# module.net
KiCad netlist of a schematic drawn in EAGLE
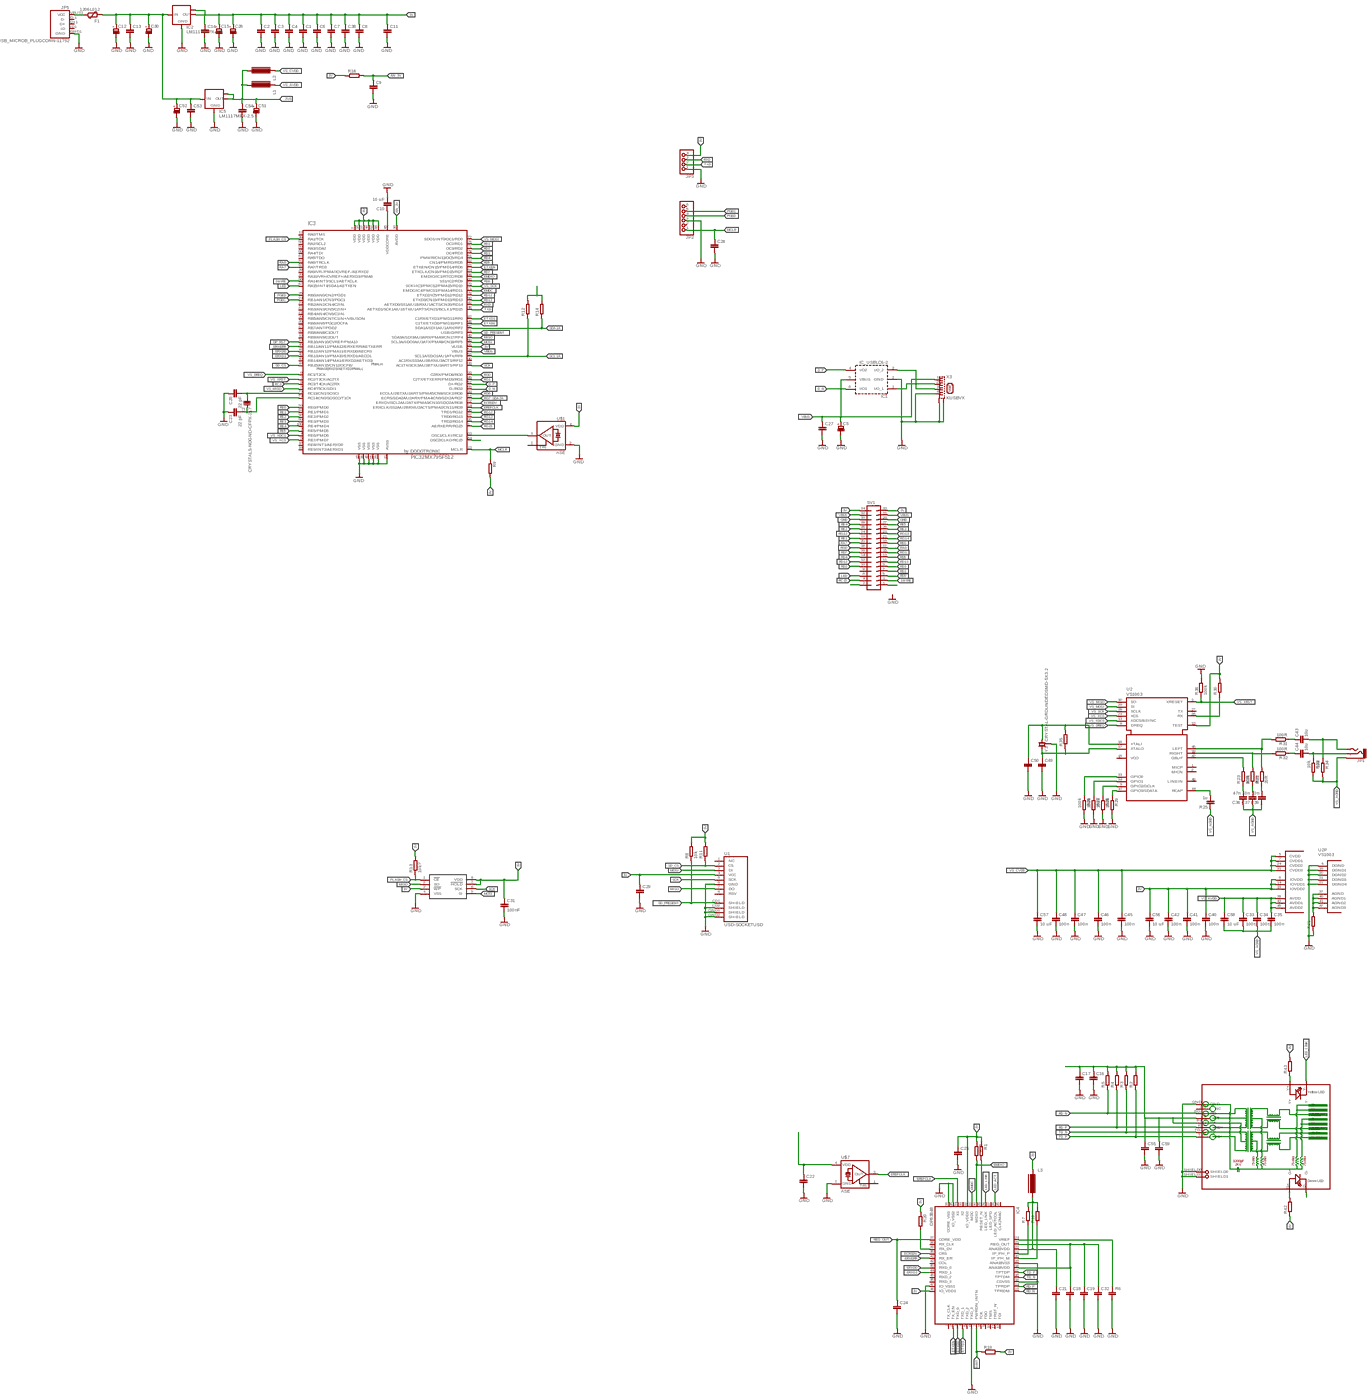
[diagram p0: schematic, sheet 1, overview]
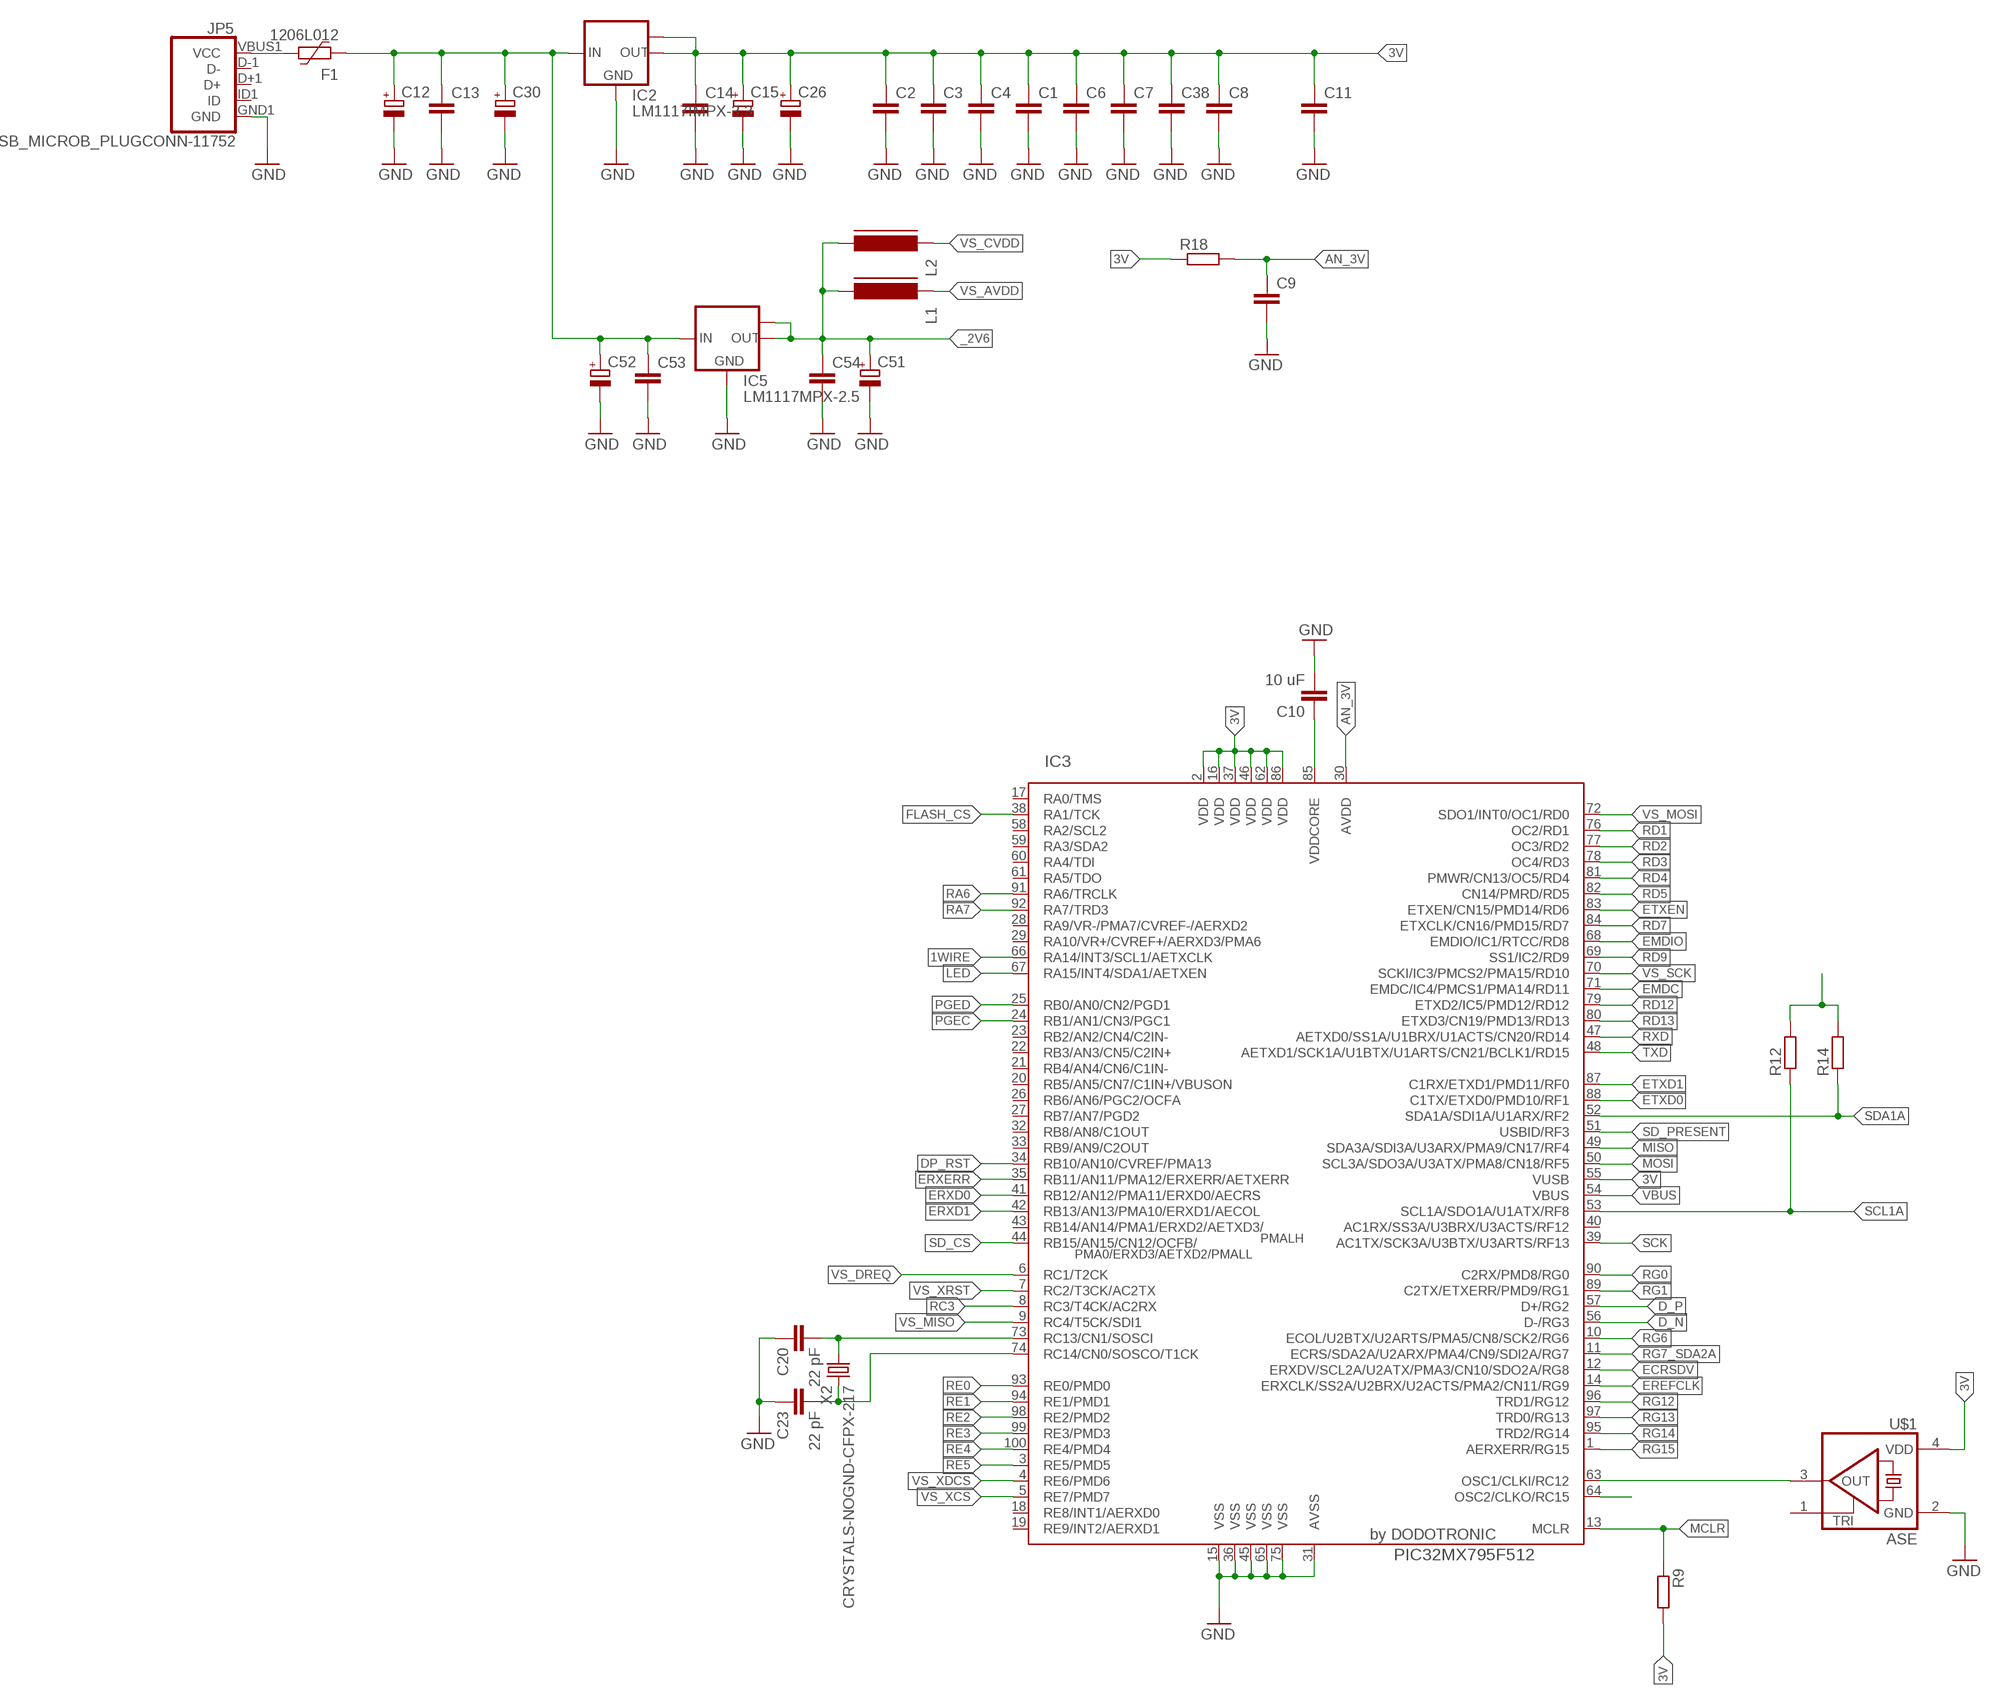
[diagram p1: schematic, sheet 1, part 1 of 4]
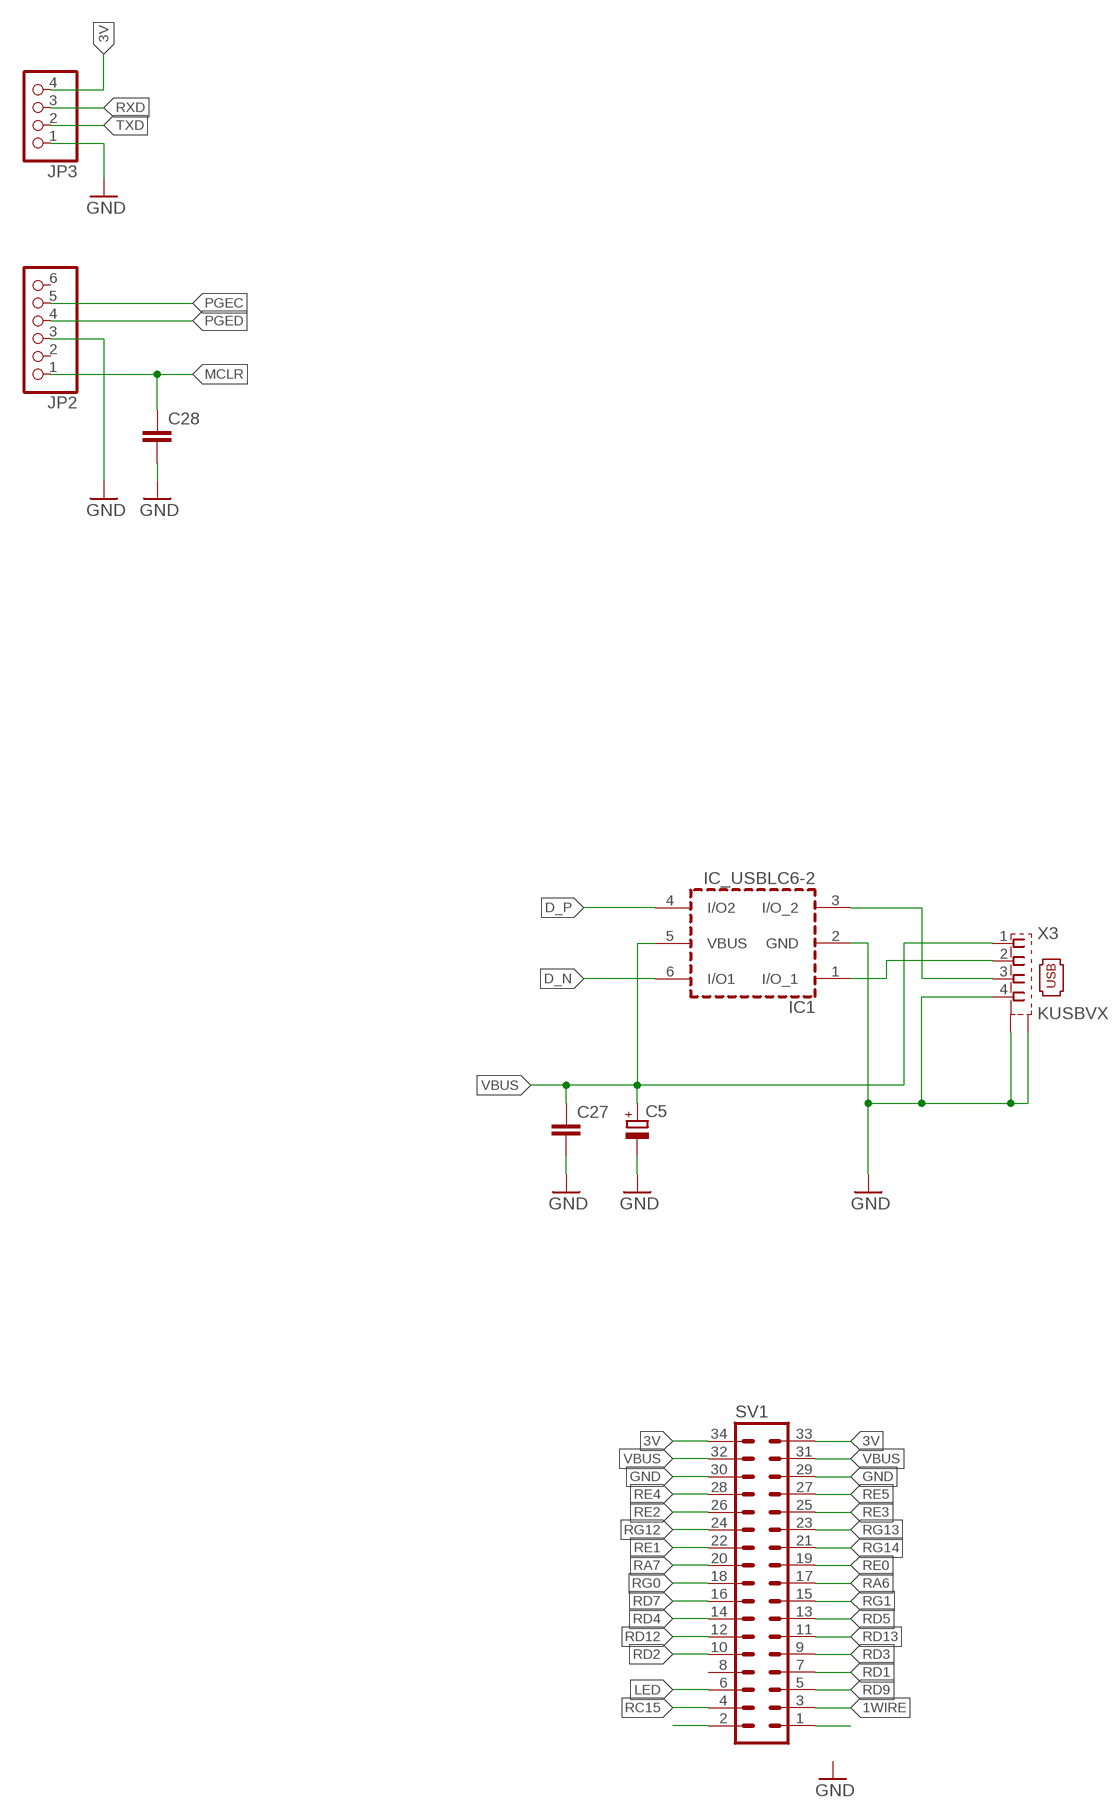
[diagram p2: schematic, sheet 1, part 2 of 4]
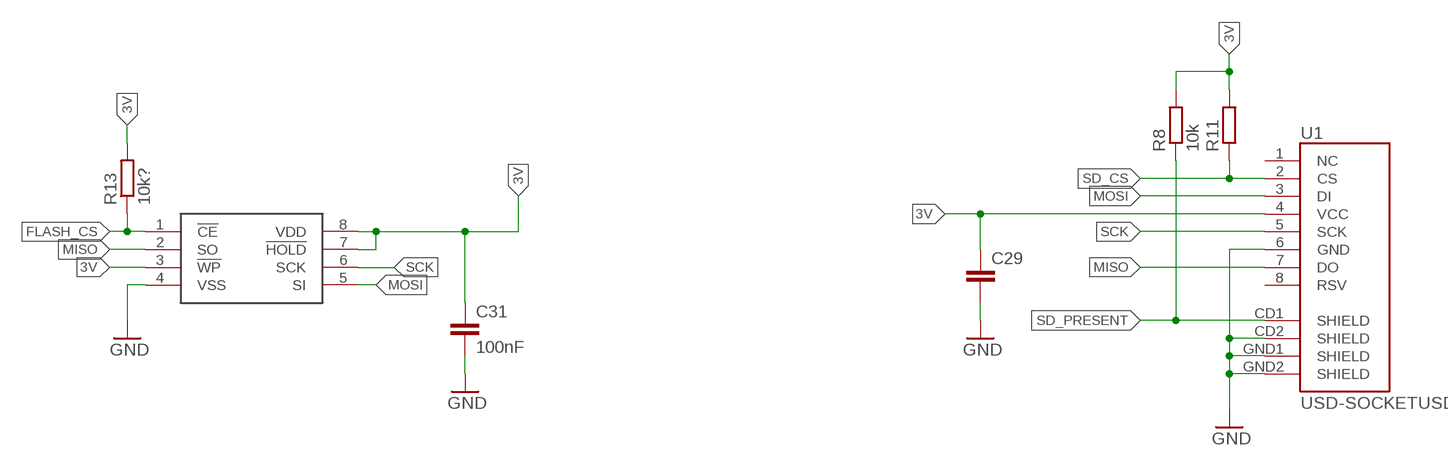
[diagram p3: schematic, sheet 1, part 3 of 4]
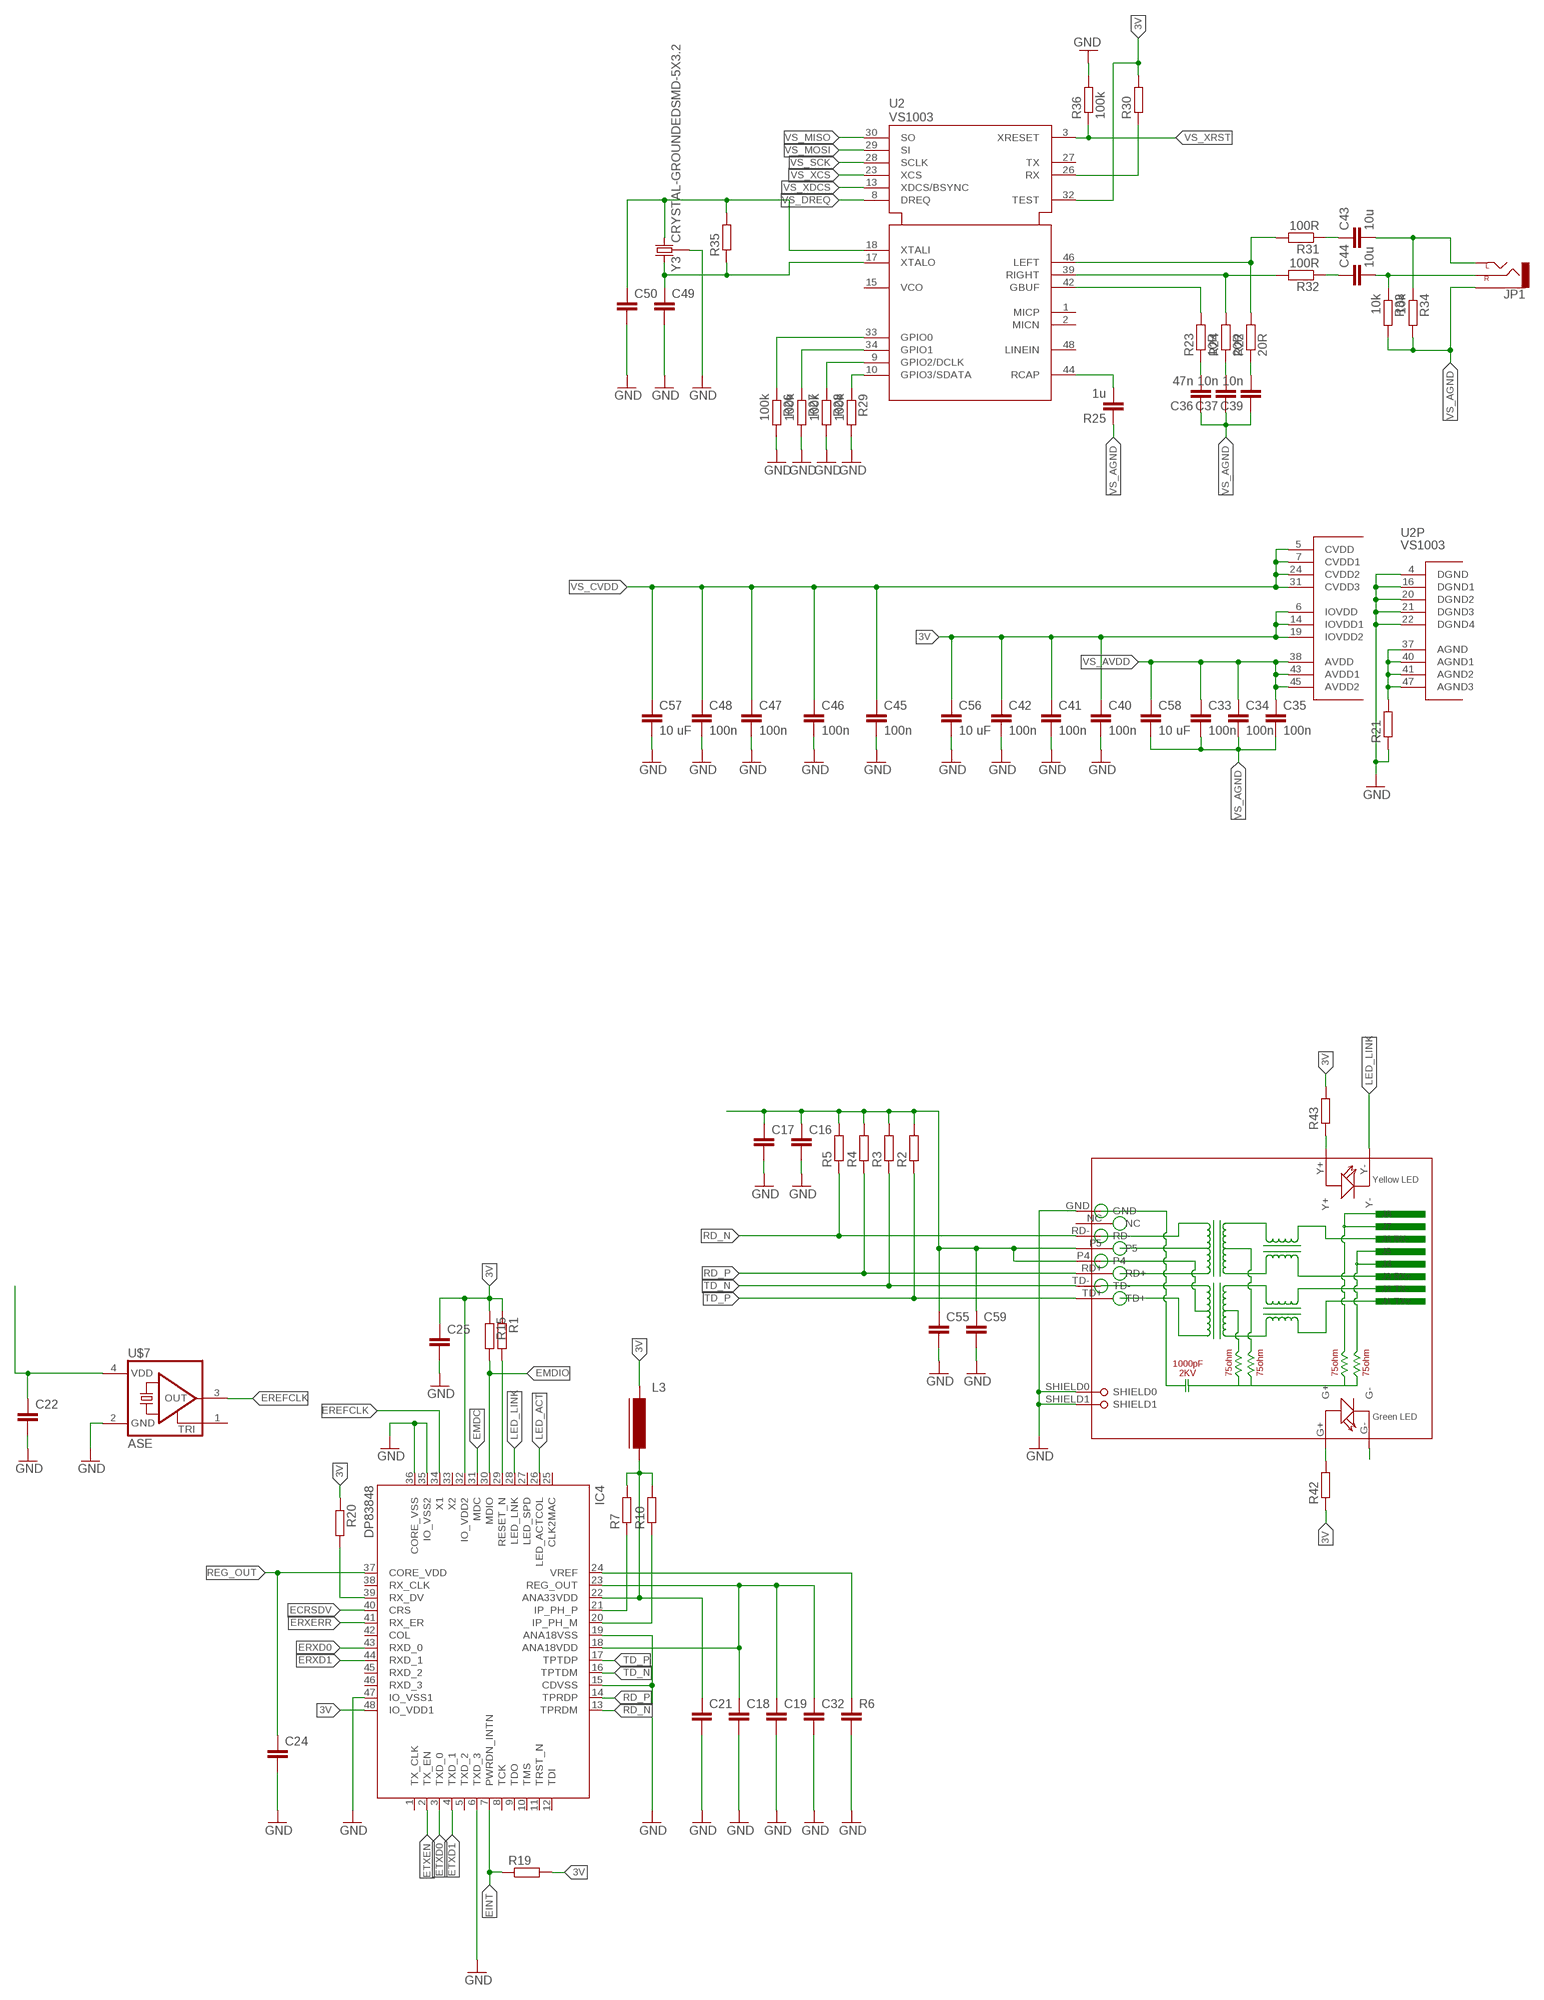
[diagram p4: schematic, sheet 1, part 4 of 4]

(export (version "E")
  (design (tool "Eeschema 10.0.6"))
  (components
    (comp (ref "C1")
      (value "C-EUC0402")
      (footprint "eagle-import:C0402")
      (libsource (lib "eagle-import") (part "C-EUC0402"))
    )
    (comp (ref "C2")
      (value "C-EUC0402")
      (footprint "eagle-import:C0402")
      (libsource (lib "eagle-import") (part "C-EUC0402"))
    )
    (comp (ref "C3")
      (value "C-EUC0402")
      (footprint "eagle-import:C0402")
      (libsource (lib "eagle-import") (part "C-EUC0402"))
    )
    (comp (ref "C4")
      (value "C-EUC0402")
      (footprint "eagle-import:C0402")
      (libsource (lib "eagle-import") (part "C-EUC0402"))
    )
    (comp (ref "C5")
      (value "CPOL-EUSMCA")
      (footprint "eagle-import:SMC_A")
      (libsource (lib "eagle-import") (part "CPOL-EUSMCA"))
    )
    (comp (ref "C6")
      (value "C-EUC0402")
      (footprint "eagle-import:C0402")
      (libsource (lib "eagle-import") (part "C-EUC0402"))
    )
    (comp (ref "C7")
      (value "C-EUC0402")
      (footprint "eagle-import:C0402")
      (libsource (lib "eagle-import") (part "C-EUC0402"))
    )
    (comp (ref "C8")
      (value "C-EUC0402")
      (footprint "eagle-import:C0402")
      (libsource (lib "eagle-import") (part "C-EUC0402"))
    )
    (comp (ref "C9")
      (value "C-EUC0402")
      (footprint "eagle-import:C0402")
      (libsource (lib "eagle-import") (part "C-EUC0402"))
    )
    (comp (ref "C10")
      (value "10 uF")
      (footprint "eagle-import:C0603")
      (libsource (lib "eagle-import") (part "C-EUC0603"))
    )
    (comp (ref "C11")
      (value "C-EUC0402")
      (footprint "eagle-import:C0402")
      (libsource (lib "eagle-import") (part "C-EUC0402"))
    )
    (comp (ref "C12")
      (value "CPOL-EUSMCB")
      (footprint "eagle-import:SMC_B")
      (libsource (lib "eagle-import") (part "CPOL-EUSMCB"))
    )
    (comp (ref "C13")
      (value "C-EUC0603")
      (footprint "eagle-import:C0603")
      (libsource (lib "eagle-import") (part "C-EUC0603"))
    )
    (comp (ref "C14")
      (value "C-EUC0603")
      (footprint "eagle-import:C0603")
      (libsource (lib "eagle-import") (part "C-EUC0603"))
    )
    (comp (ref "C15")
      (value "CPOL-EUSMCB")
      (footprint "eagle-import:SMC_B")
      (libsource (lib "eagle-import") (part "CPOL-EUSMCB"))
    )
    (comp (ref "C16")
      (value "C-EUC0603")
      (footprint "eagle-import:C0603")
      (libsource (lib "eagle-import") (part "C-EUC0603"))
    )
    (comp (ref "C17")
      (value "C-EUC0603")
      (footprint "eagle-import:C0603")
      (libsource (lib "eagle-import") (part "C-EUC0603"))
    )
    (comp (ref "C18")
      (value "C-EUC0402")
      (footprint "eagle-import:C0402")
      (libsource (lib "eagle-import") (part "C-EUC0402"))
    )
    (comp (ref "C19")
      (value "C-EUC0402")
      (footprint "eagle-import:C0402")
      (libsource (lib "eagle-import") (part "C-EUC0402"))
    )
    (comp (ref "C20")
      (value "22 pF")
      (footprint "eagle-import:C0603")
      (libsource (lib "eagle-import") (part "C-EUC0603"))
    )
    (comp (ref "C21")
      (value "C-EUC0402")
      (footprint "eagle-import:C0402")
      (libsource (lib "eagle-import") (part "C-EUC0402"))
    )
    (comp (ref "C22")
      (value "C-EUC0402")
      (footprint "eagle-import:C0402")
      (libsource (lib "eagle-import") (part "C-EUC0402"))
    )
    (comp (ref "C23")
      (value "22 pF")
      (footprint "eagle-import:C0603")
      (libsource (lib "eagle-import") (part "C-EUC0603"))
    )
    (comp (ref "C24")
      (value "C-EUC0603")
      (footprint "eagle-import:C0603")
      (libsource (lib "eagle-import") (part "C-EUC0603"))
    )
    (comp (ref "C25")
      (value "C-EUC0603")
      (footprint "eagle-import:C0603")
      (libsource (lib "eagle-import") (part "C-EUC0603"))
    )
    (comp (ref "C26")
      (value "CPOL-EUSMCA")
      (footprint "eagle-import:SMC_A")
      (libsource (lib "eagle-import") (part "CPOL-EUSMCA"))
    )
    (comp (ref "C27")
      (value "C-EUC0603")
      (footprint "eagle-import:C0603")
      (libsource (lib "eagle-import") (part "C-EUC0603"))
    )
    (comp (ref "C28")
      (value "C-EUC0603")
      (footprint "eagle-import:C0603")
      (libsource (lib "eagle-import") (part "C-EUC0603"))
    )
    (comp (ref "C29")
      (value "C-EUC0603")
      (footprint "eagle-import:C0603")
      (libsource (lib "eagle-import") (part "C-EUC0603"))
    )
    (comp (ref "C30")
      (value "CPOL-EUSMCA")
      (footprint "eagle-import:SMC_A")
      (libsource (lib "eagle-import") (part "CPOL-EUSMCA"))
    )
    (comp (ref "C31")
      (value "100nF")
      (footprint "eagle-import:C0603")
      (libsource (lib "eagle-import") (part "C-EUC0603"))
    )
    (comp (ref "C32")
      (value "C-EUC0603")
      (footprint "eagle-import:C0603")
      (libsource (lib "eagle-import") (part "C-EUC0603"))
    )
    (comp (ref "C33")
      (value "100n")
      (footprint "eagle-import:C0603")
      (libsource (lib "eagle-import") (part "C-EUC0603"))
    )
    (comp (ref "C34")
      (value "100n")
      (footprint "eagle-import:C0603")
      (libsource (lib "eagle-import") (part "C-EUC0603"))
    )
    (comp (ref "C35")
      (value "100n")
      (footprint "eagle-import:C0603")
      (libsource (lib "eagle-import") (part "C-EUC0603"))
    )
    (comp (ref "C36")
      (value "47n")
      (footprint "eagle-import:C0603")
      (libsource (lib "eagle-import") (part "C-EUC0603"))
    )
    (comp (ref "C37")
      (value "10n")
      (footprint "eagle-import:C0603")
      (libsource (lib "eagle-import") (part "C-EUC0603"))
    )
    (comp (ref "C38")
      (value "C-EUC0402")
      (footprint "eagle-import:C0402")
      (libsource (lib "eagle-import") (part "C-EUC0402"))
    )
    (comp (ref "C39")
      (value "10n")
      (footprint "eagle-import:C0603")
      (libsource (lib "eagle-import") (part "C-EUC0603"))
    )
    (comp (ref "C40")
      (value "100n")
      (footprint "eagle-import:C0402")
      (libsource (lib "eagle-import") (part "C-EUC0402"))
    )
    (comp (ref "C41")
      (value "100n")
      (footprint "eagle-import:C0402")
      (libsource (lib "eagle-import") (part "C-EUC0402"))
    )
    (comp (ref "C42")
      (value "100n")
      (footprint "eagle-import:C0402")
      (libsource (lib "eagle-import") (part "C-EUC0402"))
    )
    (comp (ref "C43")
      (value "10u")
      (footprint "eagle-import:C0603")
      (libsource (lib "eagle-import") (part "C-EUC0603"))
    )
    (comp (ref "C44")
      (value "10u")
      (footprint "eagle-import:C0603")
      (libsource (lib "eagle-import") (part "C-EUC0603"))
    )
    (comp (ref "C45")
      (value "100n")
      (footprint "eagle-import:C0402")
      (libsource (lib "eagle-import") (part "C-EUC0402"))
    )
    (comp (ref "C46")
      (value "100n")
      (footprint "eagle-import:C0603")
      (libsource (lib "eagle-import") (part "C-EUC0603"))
    )
    (comp (ref "C47")
      (value "100n")
      (footprint "eagle-import:C0603")
      (libsource (lib "eagle-import") (part "C-EUC0603"))
    )
    (comp (ref "C48")
      (value "100n")
      (footprint "eagle-import:C0603")
      (libsource (lib "eagle-import") (part "C-EUC0603"))
    )
    (comp (ref "C49")
      (value "C-EUC0603")
      (footprint "eagle-import:C0603")
      (libsource (lib "eagle-import") (part "C-EUC0603"))
    )
    (comp (ref "C50")
      (value "C-EUC0603")
      (footprint "eagle-import:C0603")
      (libsource (lib "eagle-import") (part "C-EUC0603"))
    )
    (comp (ref "C51")
      (value "CPOL-EUSMCB")
      (footprint "eagle-import:SMC_B")
      (libsource (lib "eagle-import") (part "CPOL-EUSMCB"))
    )
    (comp (ref "C52")
      (value "CPOL-EUSMCB")
      (footprint "eagle-import:SMC_B")
      (libsource (lib "eagle-import") (part "CPOL-EUSMCB"))
    )
    (comp (ref "C53")
      (value "C-EUC1206")
      (footprint "eagle-import:C1206")
      (libsource (lib "eagle-import") (part "C-EUC1206"))
    )
    (comp (ref "C54")
      (value "C-EUC1206")
      (footprint "eagle-import:C1206")
      (libsource (lib "eagle-import") (part "C-EUC1206"))
    )
    (comp (ref "C55")
      (value "C-EUC0603")
      (footprint "eagle-import:C0603")
      (libsource (lib "eagle-import") (part "C-EUC0603"))
    )
    (comp (ref "C56")
      (value "10 uF")
      (footprint "eagle-import:C0603")
      (libsource (lib "eagle-import") (part "C-EUC0603"))
    )
    (comp (ref "C57")
      (value "10 uF")
      (footprint "eagle-import:C0603")
      (libsource (lib "eagle-import") (part "C-EUC0603"))
    )
    (comp (ref "C58")
      (value "10 uF")
      (footprint "eagle-import:C0603")
      (libsource (lib "eagle-import") (part "C-EUC0603"))
    )
    (comp (ref "C59")
      (value "C-EUC0603")
      (footprint "eagle-import:C0603")
      (libsource (lib "eagle-import") (part "C-EUC0603"))
    )
    (comp (ref "F1")
      (value "1206L012")
      (footprint "eagle-import:1206L")
      (fields (field (name "MF") "Littelfuse"))
      (libsource (lib "eagle-import") (part "?1206L012"))
    )
    (comp (ref "IC1")
      (value "IC_USBLC6-2")
      (footprint "eagle-import:SOT-23-6L")
      (libsource (lib "eagle-import") (part "IC_USBLC6-2"))
    )
    (comp (ref "IC2")
      (value "LM1117IMPX-3.3")
      (footprint "eagle-import:SOT223")
      (libsource (lib "eagle-import") (part "LM1117IMPX-3.3"))
    )
    (comp (ref "IC3")
      (value "PIC32MX795F512")
      (footprint "eagle-import:TQFP100_12X12")
      (libsource (lib "eagle-import") (part "PIC32MX795F512"))
    )
    (comp (ref "IC4")
      (value "DP83848")
      (footprint "eagle-import:LQFP48")
      (fields (field (name "MPN") "DP83848VYB"))
      (libsource (lib "eagle-import") (part "DP83848"))
    )
    (comp (ref "IC5")
      (value "LM1117MPX-2.5")
      (footprint "eagle-import:SOT223")
      (libsource (lib "eagle-import") (part "LM1117MPX-2.5"))
    )
    (comp (ref "JP1")
      (value "AUDIO-JACKAUDIO_JACK2")
      (footprint "eagle-import:AUDIO-JACK2")
      (libsource (lib "eagle-import") (part "AUDIO-JACKAUDIO_JACK2"))
    )
    (comp (ref "JP2")
      (value "PINHD-1X6")
      (footprint "eagle-import:1X06")
      (libsource (lib "eagle-import") (part "PINHD-1X6"))
    )
    (comp (ref "JP3")
      (value "PINHD-1X4")
      (footprint "eagle-import:1X04")
      (libsource (lib "eagle-import") (part "PINHD-1X4"))
    )
    (comp (ref "JP5")
      (value "USB_MICROB_PLUGCONN-11752")
      (footprint "eagle-import:USB-B-MICRO-SMD_V03")
      (libsource (lib "eagle-import") (part "USB_MICROB_PLUGCONN-11752"))
    )
    (comp (ref "L1")
      (value "FERRITE-0805")
      (footprint "eagle-import:FB805")
      (libsource (lib "eagle-import") (part "FERRITE-0805"))
    )
    (comp (ref "L2")
      (value "FERRITE-0805")
      (footprint "eagle-import:FB805")
      (libsource (lib "eagle-import") (part "FERRITE-0805"))
    )
    (comp (ref "L3")
      (value "FERRITE-0805")
      (footprint "eagle-import:FB805")
      (libsource (lib "eagle-import") (part "FERRITE-0805"))
    )
    (comp (ref "R1")
      (value "R-EU_R0402")
      (footprint "eagle-import:R0402")
      (libsource (lib "eagle-import") (part "R-EU_R0402"))
    )
    (comp (ref "R2")
      (value "R-EU_R0603")
      (footprint "eagle-import:R0603")
      (libsource (lib "eagle-import") (part "R-EU_R0603"))
    )
    (comp (ref "R3")
      (value "R-EU_R0603")
      (footprint "eagle-import:R0603")
      (libsource (lib "eagle-import") (part "R-EU_R0603"))
    )
    (comp (ref "R4")
      (value "R-EU_R0603")
      (footprint "eagle-import:R0603")
      (libsource (lib "eagle-import") (part "R-EU_R0603"))
    )
    (comp (ref "R5")
      (value "R-EU_R0603")
      (footprint "eagle-import:R0603")
      (libsource (lib "eagle-import") (part "R-EU_R0603"))
    )
    (comp (ref "R6")
      (value "C-EUC0603")
      (footprint "eagle-import:C0603")
      (libsource (lib "eagle-import") (part "C-EUC0603"))
    )
    (comp (ref "R7")
      (value "R-EU_R0402")
      (footprint "eagle-import:R0402")
      (libsource (lib "eagle-import") (part "R-EU_R0402"))
    )
    (comp (ref "R8")
      (value "10k")
      (footprint "eagle-import:R0603")
      (libsource (lib "eagle-import") (part "R-EU_R0603"))
    )
    (comp (ref "R9")
      (value "R-EU_R0603")
      (footprint "eagle-import:R0603")
      (libsource (lib "eagle-import") (part "R-EU_R0603"))
    )
    (comp (ref "R10")
      (value "R-EU_R0402")
      (footprint "eagle-import:R0402")
      (libsource (lib "eagle-import") (part "R-EU_R0402"))
    )
    (comp (ref "R11")
      (value "R-EU_R0603")
      (footprint "eagle-import:R0603")
      (libsource (lib "eagle-import") (part "R-EU_R0603"))
    )
    (comp (ref "R12")
      (value "R-EU_R0603")
      (footprint "eagle-import:R0603")
      (libsource (lib "eagle-import") (part "R-EU_R0603"))
    )
    (comp (ref "R13")
      (value "10k?")
      (footprint "eagle-import:R0603")
      (libsource (lib "eagle-import") (part "R-EU_R0603"))
    )
    (comp (ref "R14")
      (value "R-EU_R0402")
      (footprint "eagle-import:R0402")
      (libsource (lib "eagle-import") (part "R-EU_R0402"))
    )
    (comp (ref "R15")
      (value "R-EU_R0603")
      (footprint "eagle-import:R0603")
      (libsource (lib "eagle-import") (part "R-EU_R0603"))
    )
    (comp (ref "R18")
      (value "R-EU_R0805")
      (footprint "eagle-import:R0805")
      (libsource (lib "eagle-import") (part "R-EU_R0805"))
    )
    (comp (ref "R19")
      (value "R-EU_R0402")
      (footprint "eagle-import:R0402")
      (libsource (lib "eagle-import") (part "R-EU_R0402"))
    )
    (comp (ref "R20")
      (value "R-EU_R0603")
      (footprint "eagle-import:R0603")
      (libsource (lib "eagle-import") (part "R-EU_R0603"))
    )
    (comp (ref "R21")
      (value "R-EU_R0603")
      (footprint "eagle-import:R0603")
      (libsource (lib "eagle-import") (part "R-EU_R0603"))
    )
    (comp (ref "R22")
      (value "20R")
      (footprint "eagle-import:R0603")
      (libsource (lib "eagle-import") (part "R-EU_R0603"))
    )
    (comp (ref "R23")
      (value "10R")
      (footprint "eagle-import:R0603")
      (libsource (lib "eagle-import") (part "R-EU_R0603"))
    )
    (comp (ref "R24")
      (value "20R")
      (footprint "eagle-import:R0603")
      (libsource (lib "eagle-import") (part "R-EU_R0603"))
    )
    (comp (ref "R25")
      (value "1u")
      (footprint "eagle-import:C0603")
      (libsource (lib "eagle-import") (part "C-EUC0603"))
    )
    (comp (ref "R26")
      (value "100k")
      (footprint "eagle-import:R0402")
      (libsource (lib "eagle-import") (part "R-EU_R0402"))
    )
    (comp (ref "R27")
      (value "100k")
      (footprint "eagle-import:R0402")
      (libsource (lib "eagle-import") (part "R-EU_R0402"))
    )
    (comp (ref "R28")
      (value "100k")
      (footprint "eagle-import:R0402")
      (libsource (lib "eagle-import") (part "R-EU_R0402"))
    )
    (comp (ref "R29")
      (value "100k")
      (footprint "eagle-import:R0402")
      (libsource (lib "eagle-import") (part "R-EU_R0402"))
    )
    (comp (ref "R30")
      (value "R-EU_0204/7")
      (footprint "eagle-import:0204_7")
      (libsource (lib "eagle-import") (part "R-EU_0204/7"))
    )
    (comp (ref "R31")
      (value "100R")
      (footprint "eagle-import:R0603")
      (libsource (lib "eagle-import") (part "R-EU_R0603"))
    )
    (comp (ref "R32")
      (value "100R")
      (footprint "eagle-import:R0603")
      (libsource (lib "eagle-import") (part "R-EU_R0603"))
    )
    (comp (ref "R33")
      (value "10k")
      (footprint "eagle-import:R0603")
      (libsource (lib "eagle-import") (part "R-EU_R0603"))
    )
    (comp (ref "R34")
      (value "10k")
      (footprint "eagle-import:R0603")
      (libsource (lib "eagle-import") (part "R-EU_R0603"))
    )
    (comp (ref "R35")
      (value "R-EU_R0603")
      (footprint "eagle-import:R0603")
      (libsource (lib "eagle-import") (part "R-EU_R0603"))
    )
    (comp (ref "R36")
      (value "100k")
      (footprint "eagle-import:R0603")
      (libsource (lib "eagle-import") (part "R-EU_R0603"))
    )
    (comp (ref "R42")
      (value "R-EU_R0603")
      (footprint "eagle-import:R0603")
      (libsource (lib "eagle-import") (part "R-EU_R0603"))
    )
    (comp (ref "R43")
      (value "R-EU_R0603")
      (footprint "eagle-import:R0603")
      (libsource (lib "eagle-import") (part "R-EU_R0603"))
    )
    (comp (ref "RJ1")
      (value "HR911105A")
      (footprint "eagle-import:HR911105A")
      (libsource (lib "eagle-import") (part "HR911105A"))
    )
    (comp (ref "SV1")
      (value "ML34L")
      (footprint "eagle-import:ML34L")
      (libsource (lib "eagle-import") (part "ML34L"))
    )
    (comp (ref "U$1")
      (value "ASE")
      (footprint "eagle-import:ASE")
      (libsource (lib "eagle-import") (part "ASE"))
    )
    (comp (ref "U$2")
      (value "SST25VF016BSO8M")
      (footprint "eagle-import:SO-08M")
      (libsource (lib "eagle-import") (part "SST25VF016BSO8M"))
    )
    (comp (ref "U$7")
      (value "ASE")
      (footprint "eagle-import:ASE")
      (libsource (lib "eagle-import") (part "ASE"))
    )
    (comp (ref "U1")
      (value "USD-SOCKETUSD")
      (footprint "eagle-import:USD-SOCKET-PP")
      (libsource (lib "eagle-import") (part "USD-SOCKETUSD"))
    )
    (comp (ref "U2")
      (value "VS1003")
      (footprint "eagle-import:LQFP48")
      (libsource (lib "eagle-import") (part "VS1003"))
    )
    (comp (ref "X2")
      (value "CRYSTALS-NOGND-CFPX-217")
      (footprint "eagle-import:3.2X1.5-2-PAD")
      (libsource (lib "eagle-import") (part "CRYSTALS-NOGND-CFPX-217"))
    )
    (comp (ref "X3")
      (value "KUSBVX")
      (footprint "eagle-import:KUSBVX")
      (libsource (lib "eagle-import") (part "KUSBVX"))
    )
    (comp (ref "Y3")
      (value "CRYSTAL-GROUNDEDSMD-5X3.2")
      (footprint "eagle-import:CRYSTAL-SMD-5X3.2-4PAD")
      (libsource (lib "eagle-import") (part "CRYSTAL-GROUNDEDSMD-5X3.2"))
    )
  )
  (nets
    (net (code "1") (name "/A3V") (class "Default")
      (node (ref "C16") (pin "1") (pinfunction "1_1") (pintype "passive"))
      (node (ref "C17") (pin "1") (pinfunction "1_1") (pintype "passive"))
      (node (ref "C21") (pin "1") (pinfunction "1_1") (pintype "passive"))
      (node (ref "C55") (pin "1") (pinfunction "1_1") (pintype "passive"))
      (node (ref "C59") (pin "1") (pinfunction "1_1") (pintype "passive"))
      (node (ref "IC4") (pin "22") (pinfunction "ANA33VDD_22") (pintype "power_in"))
      (node (ref "L3") (pin "2") (pinfunction "2_2") (pintype "passive"))
      (node (ref "R10") (pin "2") (pinfunction "2_2") (pintype "passive"))
      (node (ref "R2") (pin "2") (pinfunction "2_2") (pintype "passive"))
      (node (ref "R3") (pin "2") (pinfunction "2_2") (pintype "passive"))
      (node (ref "R4") (pin "2") (pinfunction "2_2") (pintype "passive"))
      (node (ref "R5") (pin "2") (pinfunction "2_2") (pintype "passive"))
      (node (ref "R7") (pin "2") (pinfunction "2_2") (pintype "passive"))
      (node (ref "RJ1") (pin "P4") (pinfunction "P4_P4") (pintype "bidirectional"))
      (node (ref "RJ1") (pin "P5") (pinfunction "P5_P5") (pintype "bidirectional"))
    )
    (net (code "2") (name "1WIRE") (class "Default")
      (node (ref "IC3") (pin "66") (pinfunction "RA14/INT3/SCL1/AETXCLK_66") (pintype "bidirectional"))
      (node (ref "SV1") (pin "3") (pinfunction "3_3") (pintype "passive"))
    )
    (net (code "3") (name "3V") (class "Default")
      (node (ref "C1") (pin "1") (pinfunction "1_1") (pintype "passive"))
      (node (ref "C11") (pin "1") (pinfunction "1_1") (pintype "passive"))
      (node (ref "C14") (pin "1") (pinfunction "1_1") (pintype "passive"))
      (node (ref "C15") (pin "+") (pinfunction "+_+") (pintype "passive"))
      (node (ref "C2") (pin "1") (pinfunction "1_1") (pintype "passive"))
      (node (ref "C22") (pin "1") (pinfunction "1_1") (pintype "passive"))
      (node (ref "C25") (pin "1") (pinfunction "1_1") (pintype "passive"))
      (node (ref "C26") (pin "+") (pinfunction "+_+") (pintype "passive"))
      (node (ref "C29") (pin "1") (pinfunction "1_1") (pintype "passive"))
      (node (ref "C3") (pin "1") (pinfunction "1_1") (pintype "passive"))
      (node (ref "C31") (pin "1") (pinfunction "1_1") (pintype "passive"))
      (node (ref "C38") (pin "1") (pinfunction "1_1") (pintype "passive"))
      (node (ref "C4") (pin "1") (pinfunction "1_1") (pintype "passive"))
      (node (ref "C40") (pin "1") (pinfunction "1_1") (pintype "passive"))
      (node (ref "C41") (pin "1") (pinfunction "1_1") (pintype "passive"))
      (node (ref "C42") (pin "1") (pinfunction "1_1") (pintype "passive"))
      (node (ref "C56") (pin "1") (pinfunction "1_1") (pintype "passive"))
      (node (ref "C6") (pin "1") (pinfunction "1_1") (pintype "passive"))
      (node (ref "C7") (pin "1") (pinfunction "1_1") (pintype "passive"))
      (node (ref "C8") (pin "1") (pinfunction "1_1") (pintype "passive"))
      (node (ref "IC2") (pin "2") (pinfunction "OUT_2") (pintype "passive"))
      (node (ref "IC2") (pin "TAB") (pinfunction "OUT1_TAB") (pintype "passive"))
      (node (ref "IC3") (pin "16") (pinfunction "VDD_16") (pintype "power_in"))
      (node (ref "IC3") (pin "2") (pinfunction "VDD_2") (pintype "power_in"))
      (node (ref "IC3") (pin "37") (pinfunction "VDD_37") (pintype "power_in"))
      (node (ref "IC3") (pin "46") (pinfunction "VDD_46") (pintype "power_in"))
      (node (ref "IC3") (pin "55") (pinfunction "VUSB_55") (pintype "bidirectional"))
      (node (ref "IC3") (pin "62") (pinfunction "VDD_62") (pintype "power_in"))
      (node (ref "IC3") (pin "86") (pinfunction "VDD_86") (pintype "power_in"))
      (node (ref "IC4") (pin "32") (pinfunction "IO_VDD2_32") (pintype "power_in"))
      (node (ref "IC4") (pin "48") (pinfunction "IO_VDD1_48") (pintype "power_in"))
      (node (ref "JP3") (pin "4") (pinfunction "4_4") (pintype "passive"))
      (node (ref "L3") (pin "1") (pinfunction "1_1") (pintype "passive"))
      (node (ref "R1") (pin "1") (pinfunction "1_1") (pintype "passive"))
      (node (ref "R11") (pin "2") (pinfunction "2_2") (pintype "passive"))
      (node (ref "R12") (pin "2") (pinfunction "2_2") (pintype "passive"))
      (node (ref "R13") (pin "2") (pinfunction "2_2") (pintype "passive"))
      (node (ref "R14") (pin "2") (pinfunction "2_2") (pintype "passive"))
      (node (ref "R15") (pin "1") (pinfunction "1_1") (pintype "passive"))
      (node (ref "R18") (pin "1") (pinfunction "1_1") (pintype "passive"))
      (node (ref "R19") (pin "2") (pinfunction "2_2") (pintype "passive"))
      (node (ref "R20") (pin "1") (pinfunction "1_1") (pintype "passive"))
      (node (ref "R30") (pin "2") (pinfunction "2_2") (pintype "passive"))
      (node (ref "R42") (pin "1") (pinfunction "1_1") (pintype "passive"))
      (node (ref "R43") (pin "2") (pinfunction "2_2") (pintype "passive"))
      (node (ref "R8") (pin "2") (pinfunction "2_2") (pintype "passive"))
      (node (ref "R9") (pin "2") (pinfunction "2_2") (pintype "passive"))
      (node (ref "SV1") (pin "33") (pinfunction "33_33") (pintype "passive"))
      (node (ref "SV1") (pin "34") (pinfunction "34_34") (pintype "passive"))
      (node (ref "U$1") (pin "4") (pinfunction "VDD_4") (pintype "power_in"))
      (node (ref "U$2") (pin "3") (pinfunction "~{WP}_3") (pintype "bidirectional"))
      (node (ref "U$2") (pin "7") (pinfunction "~{HOLD}_7") (pintype "bidirectional"))
      (node (ref "U$2") (pin "8") (pinfunction "VDD_8") (pintype "bidirectional"))
      (node (ref "U$7") (pin "4") (pinfunction "VDD_4") (pintype "power_in"))
      (node (ref "U1") (pin "4") (pinfunction "VCC_4") (pintype "bidirectional"))
      (node (ref "U2") (pin "14") (pinfunction "IOVDD1_14") (pintype "power_in"))
      (node (ref "U2") (pin "19") (pinfunction "IOVDD2_19") (pintype "power_in"))
      (node (ref "U2") (pin "32") (pinfunction "TEST_32") (pintype "bidirectional"))
      (node (ref "U2") (pin "6") (pinfunction "IOVDD_6") (pintype "power_in"))
    )
    (net (code "4") (name "AN_3V") (class "Default")
      (node (ref "C9") (pin "1") (pinfunction "1_1") (pintype "passive"))
      (node (ref "IC3") (pin "30") (pinfunction "AVDD_30") (pintype "bidirectional"))
      (node (ref "R18") (pin "2") (pinfunction "2_2") (pintype "passive"))
    )
    (net (code "5") (name "DP_RST") (class "Default")
      (node (ref "IC3") (pin "34") (pinfunction "RB10/AN10/CVREF/PMA13_34") (pintype "bidirectional"))
      (node (ref "IC4") (pin "29") (pinfunction "RESET_N_29") (pintype "input"))
      (node (ref "R1") (pin "2") (pinfunction "2_2") (pintype "passive"))
    )
    (net (code "6") (name "D_N") (class "Default")
      (node (ref "IC1") (pin "6") (pinfunction "I/O1_6") (pintype "bidirectional"))
      (node (ref "IC3") (pin "56") (pinfunction "D-/RG3_56") (pintype "bidirectional"))
    )
    (net (code "7") (name "D_P") (class "Default")
      (node (ref "IC1") (pin "4") (pinfunction "I/O2_4") (pintype "bidirectional"))
      (node (ref "IC3") (pin "57") (pinfunction "D+/RG2_57") (pintype "bidirectional"))
    )
    (net (code "8") (name "ECRSDV") (class "Default")
      (node (ref "IC3") (pin "12") (pinfunction "ERXDV/SCL2A/U2ATX/PMA3/CN10/SDO2A/RG8_12") (pintype "bidirectional"))
      (node (ref "IC4") (pin "40") (pinfunction "CRS_40") (pintype "bidirectional"))
    )
    (net (code "9") (name "EINT") (class "Default")
      (node (ref "IC4") (pin "7") (pinfunction "PWRDN_INTN_7") (pintype "bidirectional"))
      (node (ref "R19") (pin "1") (pinfunction "1_1") (pintype "passive"))
    )
    (net (code "10") (name "EMDC") (class "Default")
      (node (ref "IC3") (pin "71") (pinfunction "EMDC/IC4/PMCS1/PMA14/RD11_71") (pintype "bidirectional"))
      (node (ref "IC4") (pin "31") (pinfunction "MDC_31") (pintype "input"))
    )
    (net (code "11") (name "EMDIO") (class "Default")
      (node (ref "IC3") (pin "68") (pinfunction "EMDIO/IC1/RTCC/RD8_68") (pintype "bidirectional"))
      (node (ref "IC4") (pin "30") (pinfunction "MDIO_30") (pintype "bidirectional"))
      (node (ref "R15") (pin "2") (pinfunction "2_2") (pintype "passive"))
    )
    (net (code "12") (name "EREFCLK") (class "Default")
      (node (ref "IC3") (pin "14") (pinfunction "ERXCLK/SS2A/U2BRX/U2ACTS/PMA2/CN11/RG9_14") (pintype "bidirectional"))
      (node (ref "IC4") (pin "34") (pinfunction "X1_34") (pintype "input"))
      (node (ref "U$7") (pin "3") (pinfunction "OUT_3") (pintype "output"))
    )
    (net (code "13") (name "ERXD0") (class "Default")
      (node (ref "IC3") (pin "41") (pinfunction "RB12/AN12/PMA11/ERXD0/AECRS_41") (pintype "bidirectional"))
      (node (ref "IC4") (pin "43") (pinfunction "RXD_0_43") (pintype "bidirectional"))
    )
    (net (code "14") (name "ERXD1") (class "Default")
      (node (ref "IC3") (pin "42") (pinfunction "RB13/AN13/PMA10/ERXD1/AECOL_42") (pintype "bidirectional"))
      (node (ref "IC4") (pin "44") (pinfunction "RXD_1_44") (pintype "bidirectional"))
    )
    (net (code "15") (name "ERXERR") (class "Default")
      (node (ref "IC3") (pin "35") (pinfunction "RB11/AN11/PMA12/ERXERR/AETXERR_35") (pintype "bidirectional"))
      (node (ref "IC4") (pin "41") (pinfunction "RX_ER_41") (pintype "bidirectional"))
    )
    (net (code "16") (name "ETXD0") (class "Default")
      (node (ref "IC3") (pin "88") (pinfunction "C1TX/ETXD0/PMD10/RF1_88") (pintype "bidirectional"))
      (node (ref "IC4") (pin "3") (pinfunction "TXD_0_3") (pintype "bidirectional"))
    )
    (net (code "17") (name "ETXD1") (class "Default")
      (node (ref "IC3") (pin "87") (pinfunction "C1RX/ETXD1/PMD11/RF0_87") (pintype "bidirectional"))
      (node (ref "IC4") (pin "4") (pinfunction "TXD_1_4") (pintype "bidirectional"))
    )
    (net (code "18") (name "ETXEN") (class "Default")
      (node (ref "IC3") (pin "83") (pinfunction "ETXEN/CN15/PMD14/RD6_83") (pintype "bidirectional"))
      (node (ref "IC4") (pin "2") (pinfunction "TX_EN_2") (pintype "bidirectional"))
    )
    (net (code "19") (name "FLASH_CS") (class "Default")
      (node (ref "IC3") (pin "38") (pinfunction "RA1/TCK_38") (pintype "bidirectional"))
      (node (ref "R13") (pin "1") (pinfunction "1_1") (pintype "passive"))
      (node (ref "U$2") (pin "1") (pinfunction "~{CE}_1") (pintype "bidirectional"))
    )
    (net (code "20") (name "GND") (class "Default")
      (node (ref "C1") (pin "2") (pinfunction "2_2") (pintype "passive"))
      (node (ref "C10") (pin "2") (pinfunction "2_2") (pintype "passive"))
      (node (ref "C11") (pin "2") (pinfunction "2_2") (pintype "passive"))
      (node (ref "C12") (pin "-") (pinfunction "-_-") (pintype "passive"))
      (node (ref "C13") (pin "2") (pinfunction "2_2") (pintype "passive"))
      (node (ref "C14") (pin "2") (pinfunction "2_2") (pintype "passive"))
      (node (ref "C15") (pin "-") (pinfunction "-_-") (pintype "passive"))
      (node (ref "C16") (pin "2") (pinfunction "2_2") (pintype "passive"))
      (node (ref "C17") (pin "2") (pinfunction "2_2") (pintype "passive"))
      (node (ref "C18") (pin "2") (pinfunction "2_2") (pintype "passive"))
      (node (ref "C19") (pin "2") (pinfunction "2_2") (pintype "passive"))
      (node (ref "C2") (pin "2") (pinfunction "2_2") (pintype "passive"))
      (node (ref "C20") (pin "1") (pinfunction "1_1") (pintype "passive"))
      (node (ref "C21") (pin "2") (pinfunction "2_2") (pintype "passive"))
      (node (ref "C22") (pin "2") (pinfunction "2_2") (pintype "passive"))
      (node (ref "C23") (pin "1") (pinfunction "1_1") (pintype "passive"))
      (node (ref "C24") (pin "2") (pinfunction "2_2") (pintype "passive"))
      (node (ref "C25") (pin "2") (pinfunction "2_2") (pintype "passive"))
      (node (ref "C26") (pin "-") (pinfunction "-_-") (pintype "passive"))
      (node (ref "C27") (pin "2") (pinfunction "2_2") (pintype "passive"))
      (node (ref "C28") (pin "2") (pinfunction "2_2") (pintype "passive"))
      (node (ref "C29") (pin "2") (pinfunction "2_2") (pintype "passive"))
      (node (ref "C3") (pin "2") (pinfunction "2_2") (pintype "passive"))
      (node (ref "C30") (pin "-") (pinfunction "-_-") (pintype "passive"))
      (node (ref "C31") (pin "2") (pinfunction "2_2") (pintype "passive"))
      (node (ref "C32") (pin "2") (pinfunction "2_2") (pintype "passive"))
      (node (ref "C38") (pin "2") (pinfunction "2_2") (pintype "passive"))
      (node (ref "C4") (pin "2") (pinfunction "2_2") (pintype "passive"))
      (node (ref "C40") (pin "2") (pinfunction "2_2") (pintype "passive"))
      (node (ref "C41") (pin "2") (pinfunction "2_2") (pintype "passive"))
      (node (ref "C42") (pin "2") (pinfunction "2_2") (pintype "passive"))
      (node (ref "C45") (pin "2") (pinfunction "2_2") (pintype "passive"))
      (node (ref "C46") (pin "2") (pinfunction "2_2") (pintype "passive"))
      (node (ref "C47") (pin "2") (pinfunction "2_2") (pintype "passive"))
      (node (ref "C48") (pin "2") (pinfunction "2_2") (pintype "passive"))
      (node (ref "C49") (pin "2") (pinfunction "2_2") (pintype "passive"))
      (node (ref "C5") (pin "-") (pinfunction "-_-") (pintype "passive"))
      (node (ref "C50") (pin "2") (pinfunction "2_2") (pintype "passive"))
      (node (ref "C51") (pin "-") (pinfunction "-_-") (pintype "passive"))
      (node (ref "C52") (pin "-") (pinfunction "-_-") (pintype "passive"))
      (node (ref "C53") (pin "2") (pinfunction "2_2") (pintype "passive"))
      (node (ref "C54") (pin "2") (pinfunction "2_2") (pintype "passive"))
      (node (ref "C55") (pin "2") (pinfunction "2_2") (pintype "passive"))
      (node (ref "C56") (pin "2") (pinfunction "2_2") (pintype "passive"))
      (node (ref "C57") (pin "2") (pinfunction "2_2") (pintype "passive"))
      (node (ref "C59") (pin "2") (pinfunction "2_2") (pintype "passive"))
      (node (ref "C6") (pin "2") (pinfunction "2_2") (pintype "passive"))
      (node (ref "C7") (pin "2") (pinfunction "2_2") (pintype "passive"))
      (node (ref "C8") (pin "2") (pinfunction "2_2") (pintype "passive"))
      (node (ref "C9") (pin "2") (pinfunction "2_2") (pintype "passive"))
      (node (ref "IC1") (pin "2") (pinfunction "GND_2") (pintype "bidirectional"))
      (node (ref "IC2") (pin "1") (pinfunction "GND_1") (pintype "input"))
      (node (ref "IC3") (pin "15") (pinfunction "VSS_15") (pintype "power_in"))
      (node (ref "IC3") (pin "31") (pinfunction "AVSS_31") (pintype "bidirectional"))
      (node (ref "IC3") (pin "36") (pinfunction "VSS_36") (pintype "power_in"))
      (node (ref "IC3") (pin "45") (pinfunction "VSS_45") (pintype "power_in"))
      (node (ref "IC3") (pin "65") (pinfunction "VSS_65") (pintype "power_in"))
      (node (ref "IC3") (pin "75") (pinfunction "VSS_75") (pintype "power_in"))
      (node (ref "IC4") (pin "15") (pinfunction "CDVSS_15") (pintype "power_in"))
      (node (ref "IC4") (pin "19") (pinfunction "ANA18VSS_19") (pintype "power_in"))
      (node (ref "IC4") (pin "35") (pinfunction "IO_VSS2_35") (pintype "power_in"))
      (node (ref "IC4") (pin "36") (pinfunction "CORE_VSS_36") (pintype "power_in"))
      (node (ref "IC4") (pin "47") (pinfunction "IO_VSS1_47") (pintype "power_in"))
      (node (ref "IC4") (pin "6") (pinfunction "TXD_3_6") (pintype "bidirectional"))
      (node (ref "IC5") (pin "1") (pinfunction "GND_1") (pintype "input"))
      (node (ref "JP2") (pin "3") (pinfunction "3_3") (pintype "passive"))
      (node (ref "JP3") (pin "1") (pinfunction "1_1") (pintype "passive"))
      (node (ref "JP5") (pin "GND1") (pinfunction "GND_GND1") (pintype "bidirectional"))
      (node (ref "R21") (pin "1") (pinfunction "1_1") (pintype "passive"))
      (node (ref "R26") (pin "2") (pinfunction "2_2") (pintype "passive"))
      (node (ref "R27") (pin "2") (pinfunction "2_2") (pintype "passive"))
      (node (ref "R28") (pin "2") (pinfunction "2_2") (pintype "passive"))
      (node (ref "R29") (pin "2") (pinfunction "2_2") (pintype "passive"))
      (node (ref "R36") (pin "2") (pinfunction "2_2") (pintype "passive"))
      (node (ref "R6") (pin "2") (pinfunction "2_2") (pintype "passive"))
      (node (ref "RJ1") (pin "GND") (pinfunction "GND_GND") (pintype "bidirectional"))
      (node (ref "RJ1") (pin "SHIELD0") (pinfunction "SHIELD0_SHIELD0") (pintype "bidirectional"))
      (node (ref "RJ1") (pin "SHIELD1") (pinfunction "SHIELD1_SHIELD1") (pintype "bidirectional"))
      (node (ref "SV1") (pin "29") (pinfunction "29_29") (pintype "passive"))
      (node (ref "SV1") (pin "30") (pinfunction "30_30") (pintype "passive"))
      (node (ref "U$1") (pin "2") (pinfunction "GND_2") (pintype "power_in"))
      (node (ref "U$2") (pin "4") (pinfunction "VSS_4") (pintype "bidirectional"))
      (node (ref "U$7") (pin "2") (pinfunction "GND_2") (pintype "power_in"))
      (node (ref "U1") (pin "6") (pinfunction "GND_6") (pintype "bidirectional"))
      (node (ref "U1") (pin "CD2") (pinfunction "SHIELD_CD2") (pintype "bidirectional"))
      (node (ref "U1") (pin "GND1") (pinfunction "SHIELD_GND1") (pintype "bidirectional"))
      (node (ref "U1") (pin "GND2") (pinfunction "SHIELD_GND2") (pintype "bidirectional"))
      (node (ref "U2") (pin "16") (pinfunction "DGND1_16") (pintype "power_in"))
      (node (ref "U2") (pin "20") (pinfunction "DGND2_20") (pintype "power_in"))
      (node (ref "U2") (pin "21") (pinfunction "DGND3_21") (pintype "power_in"))
      (node (ref "U2") (pin "22") (pinfunction "DGND4_22") (pintype "power_in"))
      (node (ref "U2") (pin "4") (pinfunction "DGND_4") (pintype "power_in"))
      (node (ref "X3") (pin "4") (pinfunction "4_4") (pintype "passive"))
      (node (ref "X3") (pin "M1") (pinfunction "S1_M1") (pintype "passive"))
      (node (ref "X3") (pin "M2") (pinfunction "S2_M2") (pintype "passive"))
      (node (ref "Y3") (pin "2") (pinfunction "3_2") (pintype "passive"))
      (node (ref "Y3") (pin "4") (pinfunction "3_4") (pintype "passive"))
    )
    (net (code "21") (name "LED") (class "Default")
      (node (ref "IC3") (pin "67") (pinfunction "RA15/INT4/SDA1/AETXEN_67") (pintype "bidirectional"))
      (node (ref "SV1") (pin "6") (pinfunction "6_6") (pintype "passive"))
    )
    (net (code "22") (name "LED_ACT") (class "Default")
      (node (ref "IC4") (pin "26") (pinfunction "LED_ACTCOL_26") (pintype "bidirectional"))
      (node (ref "RJ1") (pin "G-") (pinfunction "G-_G-") (pintype "bidirectional"))
    )
    (net (code "23") (name "LED_LINK") (class "Default")
      (node (ref "IC4") (pin "28") (pinfunction "LED_LNK_28") (pintype "bidirectional"))
      (node (ref "RJ1") (pin "Y-") (pinfunction "Y-_Y-") (pintype "bidirectional"))
    )
    (net (code "24") (name "MCLR") (class "Default")
      (node (ref "C28") (pin "1") (pinfunction "1_1") (pintype "passive"))
      (node (ref "IC3") (pin "13") (pinfunction "MCLR_13") (pintype "bidirectional"))
      (node (ref "JP2") (pin "1") (pinfunction "1_1") (pintype "passive"))
      (node (ref "R9") (pin "1") (pinfunction "1_1") (pintype "passive"))
    )
    (net (code "25") (name "MISO") (class "Default")
      (node (ref "IC3") (pin "49") (pinfunction "SDA3A/SDI3A/U3ARX/PMA9/CN17/RF4_49") (pintype "bidirectional"))
      (node (ref "U$2") (pin "2") (pinfunction "SO_2") (pintype "bidirectional"))
      (node (ref "U1") (pin "7") (pinfunction "DO_7") (pintype "bidirectional"))
    )
    (net (code "26") (name "MOSI") (class "Default")
      (node (ref "IC3") (pin "50") (pinfunction "SCL3A/SDO3A/U3ATX/PMA8/CN18/RF5_50") (pintype "bidirectional"))
      (node (ref "U$2") (pin "5") (pinfunction "SI_5") (pintype "bidirectional"))
      (node (ref "U1") (pin "3") (pinfunction "DI_3") (pintype "bidirectional"))
    )
    (net (code "27") (name "Net-(C36-Pad2)") (class "Default")
      (node (ref "C36") (pin "2") (pinfunction "2_2") (pintype "passive"))
      (node (ref "R23") (pin "1") (pinfunction "1_1") (pintype "passive"))
    )
    (net (code "28") (name "Net-(C37-Pad2)") (class "Default")
      (node (ref "C37") (pin "2") (pinfunction "2_2") (pintype "passive"))
      (node (ref "R24") (pin "1") (pinfunction "1_1") (pintype "passive"))
    )
    (net (code "29") (name "Net-(C39-Pad2)") (class "Default")
      (node (ref "C39") (pin "2") (pinfunction "2_2") (pintype "passive"))
      (node (ref "R22") (pin "1") (pinfunction "1_1") (pintype "passive"))
    )
    (net (code "30") (name "Net-(C43-Pad1)") (class "Default")
      (node (ref "C43") (pin "1") (pinfunction "1_1") (pintype "passive"))
      (node (ref "R31") (pin "1") (pinfunction "1_1") (pintype "passive"))
    )
    (net (code "31") (name "Net-(C44-Pad1)") (class "Default")
      (node (ref "C44") (pin "1") (pinfunction "1_1") (pintype "passive"))
      (node (ref "R32") (pin "1") (pinfunction "1_1") (pintype "passive"))
    )
    (net (code "32") (name "Net-(IC1-I{slash}O_1)") (class "Default")
      (node (ref "IC1") (pin "1") (pinfunction "I/O_1_1") (pintype "bidirectional"))
      (node (ref "X3") (pin "2") (pinfunction "2_2") (pintype "passive"))
    )
    (net (code "33") (name "Net-(IC1-I{slash}O_2)") (class "Default")
      (node (ref "IC1") (pin "3") (pinfunction "I/O_2_3") (pintype "bidirectional"))
      (node (ref "X3") (pin "3") (pinfunction "3_3") (pintype "passive"))
    )
    (net (code "34") (name "Net-(IC3-OSC1{slash}CLKI{slash}RC12)") (class "Default")
      (node (ref "IC3") (pin "63") (pinfunction "OSC1/CLKI/RC12_63") (pintype "bidirectional"))
      (node (ref "U$1") (pin "3") (pinfunction "OUT_3") (pintype "output"))
    )
    (net (code "35") (name "Net-(IC3-RC13{slash}CN1{slash}SOSCI)") (class "Default")
      (node (ref "C20") (pin "2") (pinfunction "2_2") (pintype "passive"))
      (node (ref "IC3") (pin "73") (pinfunction "RC13/CN1/SOSCI_73") (pintype "bidirectional"))
      (node (ref "X2") (pin "1") (pinfunction "1_1") (pintype "passive"))
    )
    (net (code "36") (name "Net-(IC3-RC14{slash}CN0{slash}SOSCO{slash}T1CK)") (class "Default")
      (node (ref "C23") (pin "2") (pinfunction "2_2") (pintype "passive"))
      (node (ref "IC3") (pin "74") (pinfunction "RC14/CN0/SOSCO/T1CK_74") (pintype "bidirectional"))
      (node (ref "X2") (pin "2") (pinfunction "2_2") (pintype "passive"))
    )
    (net (code "37") (name "Net-(IC3-VDDCORE)") (class "Default")
      (node (ref "C10") (pin "1") (pinfunction "1_1") (pintype "passive"))
      (node (ref "IC3") (pin "85") (pinfunction "VDDCORE_85") (pintype "bidirectional"))
    )
    (net (code "38") (name "Net-(IC4-IP_PH_M)") (class "Default")
      (node (ref "IC4") (pin "20") (pinfunction "IP_PH_M_20") (pintype "input"))
      (node (ref "R10") (pin "1") (pinfunction "1_1") (pintype "passive"))
    )
    (net (code "39") (name "Net-(IC4-IP_PH_P)") (class "Default")
      (node (ref "IC4") (pin "21") (pinfunction "IP_PH_P_21") (pintype "input"))
      (node (ref "R7") (pin "1") (pinfunction "1_1") (pintype "passive"))
    )
    (net (code "40") (name "Net-(IC4-RX_DV)") (class "Default")
      (node (ref "IC4") (pin "39") (pinfunction "RX_DV_39") (pintype "bidirectional"))
      (node (ref "R20") (pin "2") (pinfunction "2_2") (pintype "passive"))
    )
    (net (code "41") (name "Net-(IC4-VREF)") (class "Default")
      (node (ref "IC4") (pin "24") (pinfunction "VREF_24") (pintype "bidirectional"))
      (node (ref "R6") (pin "1") (pinfunction "1_1") (pintype "passive"))
    )
    (net (code "42") (name "Net-(JP1-LEFT)") (class "Default")
      (node (ref "C43") (pin "2") (pinfunction "2_2") (pintype "passive"))
      (node (ref "JP1") (pin "TIP") (pinfunction "LEFT_TIP") (pintype "bidirectional"))
      (node (ref "R34") (pin "1") (pinfunction "1_1") (pintype "passive"))
    )
    (net (code "43") (name "Net-(JP1-RIGHT)") (class "Default")
      (node (ref "C44") (pin "2") (pinfunction "2_2") (pintype "passive"))
      (node (ref "JP1") (pin "RING") (pinfunction "RIGHT_RING") (pintype "bidirectional"))
      (node (ref "R33") (pin "1") (pinfunction "1_1") (pintype "passive"))
    )
    (net (code "44") (name "Net-(JP5-VCC)") (class "Default")
      (node (ref "F1") (pin "1") (pinfunction "1_1") (pintype "passive"))
      (node (ref "JP5") (pin "VBUS1") (pinfunction "VCC_VBUS1") (pintype "bidirectional"))
    )
    (net (code "45") (name "Net-(R42-Pad2)") (class "Default")
      (node (ref "R42") (pin "2") (pinfunction "2_2") (pintype "passive"))
      (node (ref "RJ1") (pin "G+") (pinfunction "G+_G+") (pintype "bidirectional"))
    )
    (net (code "46") (name "Net-(R43-Pad1)") (class "Default")
      (node (ref "R43") (pin "1") (pinfunction "1_1") (pintype "passive"))
      (node (ref "RJ1") (pin "Y+") (pinfunction "Y+_Y+") (pintype "bidirectional"))
    )
    (net (code "47") (name "Net-(U2A-GBUF)") (class "Default")
      (node (ref "R23") (pin "2") (pinfunction "2_2") (pintype "passive"))
      (node (ref "U2") (pin "42") (pinfunction "GBUF_42") (pintype "bidirectional"))
    )
    (net (code "48") (name "Net-(U2A-GPIO0)") (class "Default")
      (node (ref "R26") (pin "1") (pinfunction "1_1") (pintype "passive"))
      (node (ref "U2") (pin "33") (pinfunction "GPIO0_33") (pintype "bidirectional"))
    )
    (net (code "49") (name "Net-(U2A-GPIO1)") (class "Default")
      (node (ref "R27") (pin "1") (pinfunction "1_1") (pintype "passive"))
      (node (ref "U2") (pin "34") (pinfunction "GPIO1_34") (pintype "bidirectional"))
    )
    (net (code "50") (name "Net-(U2A-GPIO2{slash}DCLK)") (class "Default")
      (node (ref "R28") (pin "1") (pinfunction "1_1") (pintype "passive"))
      (node (ref "U2") (pin "9") (pinfunction "GPIO2/DCLK_9") (pintype "bidirectional"))
    )
    (net (code "51") (name "Net-(U2A-GPIO3{slash}SDATA)") (class "Default")
      (node (ref "R29") (pin "1") (pinfunction "1_1") (pintype "passive"))
      (node (ref "U2") (pin "10") (pinfunction "GPIO3/SDATA_10") (pintype "bidirectional"))
    )
    (net (code "52") (name "Net-(U2A-LEFT)") (class "Default")
      (node (ref "R22") (pin "2") (pinfunction "2_2") (pintype "passive"))
      (node (ref "R31") (pin "2") (pinfunction "2_2") (pintype "passive"))
      (node (ref "U2") (pin "46") (pinfunction "LEFT_46") (pintype "bidirectional"))
    )
    (net (code "53") (name "Net-(U2A-RCAP)") (class "Default")
      (node (ref "R25") (pin "2") (pinfunction "2_2") (pintype "passive"))
      (node (ref "U2") (pin "44") (pinfunction "RCAP_44") (pintype "bidirectional"))
    )
    (net (code "54") (name "Net-(U2A-RIGHT)") (class "Default")
      (node (ref "R24") (pin "2") (pinfunction "2_2") (pintype "passive"))
      (node (ref "R32") (pin "2") (pinfunction "2_2") (pintype "passive"))
      (node (ref "U2") (pin "39") (pinfunction "RIGHT_39") (pintype "bidirectional"))
    )
    (net (code "55") (name "Net-(U2A-RX)") (class "Default")
      (node (ref "R30") (pin "1") (pinfunction "1_1") (pintype "passive"))
      (node (ref "U2") (pin "26") (pinfunction "RX_26") (pintype "bidirectional"))
    )
    (net (code "56") (name "Net-(U2A-XTALI)") (class "Default")
      (node (ref "C50") (pin "1") (pinfunction "1_1") (pintype "passive"))
      (node (ref "R35") (pin "2") (pinfunction "2_2") (pintype "passive"))
      (node (ref "U2") (pin "18") (pinfunction "XTALI_18") (pintype "bidirectional"))
      (node (ref "Y3") (pin "1") (pinfunction "2_1") (pintype "passive"))
    )
    (net (code "57") (name "Net-(U2A-XTALO)") (class "Default")
      (node (ref "C49") (pin "1") (pinfunction "1_1") (pintype "passive"))
      (node (ref "R35") (pin "1") (pinfunction "1_1") (pintype "passive"))
      (node (ref "U2") (pin "17") (pinfunction "XTALO_17") (pintype "bidirectional"))
      (node (ref "Y3") (pin "3") (pinfunction "1_3") (pintype "passive"))
    )
    (net (code "58") (name "PGEC") (class "Default")
      (node (ref "IC3") (pin "24") (pinfunction "RB1/AN1/CN3/PGC1_24") (pintype "bidirectional"))
      (node (ref "JP2") (pin "5") (pinfunction "5_5") (pintype "passive"))
    )
    (net (code "59") (name "PGED") (class "Default")
      (node (ref "IC3") (pin "25") (pinfunction "RB0/AN0/CN2/PGD1_25") (pintype "bidirectional"))
      (node (ref "JP2") (pin "4") (pinfunction "4_4") (pintype "passive"))
    )
    (net (code "60") (name "RA6") (class "Default")
      (node (ref "IC3") (pin "91") (pinfunction "RA6/TRCLK_91") (pintype "bidirectional"))
      (node (ref "SV1") (pin "17") (pinfunction "17_17") (pintype "passive"))
    )
    (net (code "61") (name "RA7") (class "Default")
      (node (ref "IC3") (pin "92") (pinfunction "RA7/TRD3_92") (pintype "bidirectional"))
      (node (ref "SV1") (pin "20") (pinfunction "20_20") (pintype "passive"))
    )
    (net (code "62") (name "RC3") (class "Default")
      (node (ref "IC3") (pin "8") (pinfunction "RC3/T4CK/AC2RX_8") (pintype "bidirectional"))
    )
    (net (code "63") (name "RC15") (class "Default")
      (node (ref "IC3") (pin "64") (pinfunction "OSC2/CLKO/RC15_64") (pintype "bidirectional"))
      (node (ref "SV1") (pin "4") (pinfunction "4_4") (pintype "passive"))
    )
    (net (code "64") (name "RD1") (class "Default")
      (node (ref "IC3") (pin "76") (pinfunction "OC2/RD1_76") (pintype "bidirectional"))
      (node (ref "SV1") (pin "7") (pinfunction "7_7") (pintype "passive"))
    )
    (net (code "65") (name "RD2") (class "Default")
      (node (ref "IC3") (pin "77") (pinfunction "OC3/RD2_77") (pintype "bidirectional"))
      (node (ref "SV1") (pin "10") (pinfunction "10_10") (pintype "passive"))
    )
    (net (code "66") (name "RD3") (class "Default")
      (node (ref "IC3") (pin "78") (pinfunction "OC4/RD3_78") (pintype "bidirectional"))
      (node (ref "SV1") (pin "9") (pinfunction "9_9") (pintype "passive"))
    )
    (net (code "67") (name "RD4") (class "Default")
      (node (ref "IC3") (pin "81") (pinfunction "PMWR/CN13/OC5/RD4_81") (pintype "bidirectional"))
      (node (ref "SV1") (pin "14") (pinfunction "14_14") (pintype "passive"))
    )
    (net (code "68") (name "RD5") (class "Default")
      (node (ref "IC3") (pin "82") (pinfunction "CN14/PMRD/RD5_82") (pintype "bidirectional"))
      (node (ref "SV1") (pin "13") (pinfunction "13_13") (pintype "passive"))
    )
    (net (code "69") (name "RD7") (class "Default")
      (node (ref "IC3") (pin "84") (pinfunction "ETXCLK/CN16/PMD15/RD7_84") (pintype "bidirectional"))
      (node (ref "SV1") (pin "16") (pinfunction "16_16") (pintype "passive"))
    )
    (net (code "70") (name "RD9") (class "Default")
      (node (ref "IC3") (pin "69") (pinfunction "SS1/IC2/RD9_69") (pintype "bidirectional"))
      (node (ref "SV1") (pin "5") (pinfunction "5_5") (pintype "passive"))
    )
    (net (code "71") (name "RD12") (class "Default")
      (node (ref "IC3") (pin "79") (pinfunction "ETXD2/IC5/PMD12/RD12_79") (pintype "bidirectional"))
      (node (ref "SV1") (pin "12") (pinfunction "12_12") (pintype "passive"))
    )
    (net (code "72") (name "RD13") (class "Default")
      (node (ref "IC3") (pin "80") (pinfunction "ETXD3/CN19/PMD13/RD13_80") (pintype "bidirectional"))
      (node (ref "SV1") (pin "11") (pinfunction "11_11") (pintype "passive"))
    )
    (net (code "73") (name "RD_N") (class "Default")
      (node (ref "IC4") (pin "13") (pinfunction "TPRDM_13") (pintype "bidirectional"))
      (node (ref "R5") (pin "1") (pinfunction "1_1") (pintype "passive"))
      (node (ref "RJ1") (pin "RD-") (pinfunction "RD-_RD-") (pintype "bidirectional"))
    )
    (net (code "74") (name "RD_P") (class "Default")
      (node (ref "IC4") (pin "14") (pinfunction "TPRDP_14") (pintype "bidirectional"))
      (node (ref "R4") (pin "1") (pinfunction "1_1") (pintype "passive"))
      (node (ref "RJ1") (pin "RD+") (pinfunction "RD+_RD+") (pintype "bidirectional"))
    )
    (net (code "75") (name "RE0") (class "Default")
      (node (ref "IC3") (pin "93") (pinfunction "RE0/PMD0_93") (pintype "bidirectional"))
      (node (ref "SV1") (pin "19") (pinfunction "19_19") (pintype "passive"))
    )
    (net (code "76") (name "RE1") (class "Default")
      (node (ref "IC3") (pin "94") (pinfunction "RE1/PMD1_94") (pintype "bidirectional"))
      (node (ref "SV1") (pin "22") (pinfunction "22_22") (pintype "passive"))
    )
    (net (code "77") (name "RE2") (class "Default")
      (node (ref "IC3") (pin "98") (pinfunction "RE2/PMD2_98") (pintype "bidirectional"))
      (node (ref "SV1") (pin "26") (pinfunction "26_26") (pintype "passive"))
    )
    (net (code "78") (name "RE3") (class "Default")
      (node (ref "IC3") (pin "99") (pinfunction "RE3/PMD3_99") (pintype "bidirectional"))
      (node (ref "SV1") (pin "25") (pinfunction "25_25") (pintype "passive"))
    )
    (net (code "79") (name "RE4") (class "Default")
      (node (ref "IC3") (pin "100") (pinfunction "RE4/PMD4_100") (pintype "bidirectional"))
      (node (ref "SV1") (pin "28") (pinfunction "28_28") (pintype "passive"))
    )
    (net (code "80") (name "RE5") (class "Default")
      (node (ref "IC3") (pin "3") (pinfunction "RE5/PMD5_3") (pintype "bidirectional"))
      (node (ref "SV1") (pin "27") (pinfunction "27_27") (pintype "passive"))
    )
    (net (code "81") (name "REG_OUT") (class "Default")
      (node (ref "C18") (pin "1") (pinfunction "1_1") (pintype "passive"))
      (node (ref "C19") (pin "1") (pinfunction "1_1") (pintype "passive"))
      (node (ref "C24") (pin "1") (pinfunction "1_1") (pintype "passive"))
      (node (ref "C32") (pin "1") (pinfunction "1_1") (pintype "passive"))
      (node (ref "IC4") (pin "18") (pinfunction "ANA18VDD_18") (pintype "power_in"))
      (node (ref "IC4") (pin "23") (pinfunction "REG_OUT_23") (pintype "output"))
      (node (ref "IC4") (pin "37") (pinfunction "CORE_VDD_37") (pintype "power_in"))
    )
    (net (code "82") (name "RG0") (class "Default")
      (node (ref "IC3") (pin "90") (pinfunction "C2RX/PMD8/RG0_90") (pintype "bidirectional"))
      (node (ref "SV1") (pin "18") (pinfunction "18_18") (pintype "passive"))
    )
    (net (code "83") (name "RG1") (class "Default")
      (node (ref "IC3") (pin "89") (pinfunction "C2TX/ETXERR/PMD9/RG1_89") (pintype "bidirectional"))
      (node (ref "SV1") (pin "15") (pinfunction "15_15") (pintype "passive"))
    )
    (net (code "84") (name "RG6") (class "Default")
      (node (ref "IC3") (pin "10") (pinfunction "ECOL/U2BTX/U2ARTS/PMA5/CN8/SCK2/RG6_10") (pintype "bidirectional"))
    )
    (net (code "85") (name "RG7_SDA2A") (class "Default")
      (node (ref "IC3") (pin "11") (pinfunction "ECRS/SDA2A/U2ARX/PMA4/CN9/SDI2A/RG7_11") (pintype "bidirectional"))
    )
    (net (code "86") (name "RG12") (class "Default")
      (node (ref "IC3") (pin "96") (pinfunction "TRD1/RG12_96") (pintype "bidirectional"))
      (node (ref "SV1") (pin "24") (pinfunction "24_24") (pintype "passive"))
    )
    (net (code "87") (name "RG13") (class "Default")
      (node (ref "IC3") (pin "97") (pinfunction "TRD0/RG13_97") (pintype "bidirectional"))
      (node (ref "SV1") (pin "23") (pinfunction "23_23") (pintype "passive"))
    )
    (net (code "88") (name "RG14") (class "Default")
      (node (ref "IC3") (pin "95") (pinfunction "TRD2/RG14_95") (pintype "bidirectional"))
      (node (ref "SV1") (pin "21") (pinfunction "21_21") (pintype "passive"))
    )
    (net (code "89") (name "RG15") (class "Default")
      (node (ref "IC3") (pin "1") (pinfunction "AERXERR/RG15_1") (pintype "bidirectional"))
    )
    (net (code "90") (name "RXD") (class "Default")
      (node (ref "IC3") (pin "47") (pinfunction "AETXD0/SS1A/U1BRX/U1ACTS/CN20/RD14_47") (pintype "bidirectional"))
      (node (ref "JP3") (pin "3") (pinfunction "3_3") (pintype "passive"))
    )
    (net (code "91") (name "SCK") (class "Default")
      (node (ref "IC3") (pin "39") (pinfunction "AC1TX/SCK3A/U3BTX/U3ARTS/RF13_39") (pintype "bidirectional"))
      (node (ref "U$2") (pin "6") (pinfunction "SCK_6") (pintype "bidirectional"))
      (node (ref "U1") (pin "5") (pinfunction "SCK_5") (pintype "bidirectional"))
    )
    (net (code "92") (name "SCL1A") (class "Default")
      (node (ref "IC3") (pin "53") (pinfunction "SCL1A/SDO1A/U1ATX/RF8_53") (pintype "bidirectional"))
      (node (ref "R12") (pin "1") (pinfunction "1_1") (pintype "passive"))
      (node (ref "SV1") (pin "1") (pinfunction "1_1") (pintype "passive"))
    )
    (net (code "93") (name "SDA1A") (class "Default")
      (node (ref "IC3") (pin "52") (pinfunction "SDA1A/SDI1A/U1ARX/RF2_52") (pintype "bidirectional"))
      (node (ref "R14") (pin "1") (pinfunction "1_1") (pintype "passive"))
      (node (ref "SV1") (pin "2") (pinfunction "2_2") (pintype "passive"))
    )
    (net (code "94") (name "SD_CS") (class "Default")
      (node (ref "IC3") (pin "44") (pinfunction "RB15/AN15/CN12/OCFB/_44") (pintype "bidirectional"))
      (node (ref "R11") (pin "1") (pinfunction "1_1") (pintype "passive"))
      (node (ref "U1") (pin "2") (pinfunction "CS_2") (pintype "bidirectional"))
    )
    (net (code "95") (name "SD_PRESENT") (class "Default")
      (node (ref "IC3") (pin "51") (pinfunction "USBID/RF3_51") (pintype "bidirectional"))
      (node (ref "R8") (pin "1") (pinfunction "1_1") (pintype "passive"))
      (node (ref "U1") (pin "CD1") (pinfunction "SHIELD_CD1") (pintype "bidirectional"))
    )
    (net (code "96") (name "TD_N") (class "Default")
      (node (ref "IC4") (pin "16") (pinfunction "TPTDM_16") (pintype "bidirectional"))
      (node (ref "R3") (pin "1") (pinfunction "1_1") (pintype "passive"))
      (node (ref "RJ1") (pin "TD-") (pinfunction "TD-_TD-") (pintype "bidirectional"))
    )
    (net (code "97") (name "TD_P") (class "Default")
      (node (ref "IC4") (pin "17") (pinfunction "TPTDP_17") (pintype "bidirectional"))
      (node (ref "R2") (pin "1") (pinfunction "1_1") (pintype "passive"))
      (node (ref "RJ1") (pin "TD+") (pinfunction "TD+_TD+") (pintype "bidirectional"))
    )
    (net (code "98") (name "TXD") (class "Default")
      (node (ref "IC3") (pin "48") (pinfunction "AETXD1/SCK1A/U1BTX/U1ARTS/CN21/BCLK1/RD15_48") (pintype "bidirectional"))
      (node (ref "JP3") (pin "2") (pinfunction "2_2") (pintype "passive"))
    )
    (net (code "99") (name "VBUS") (class "Default")
      (node (ref "C12") (pin "+") (pinfunction "+_+") (pintype "passive"))
      (node (ref "C13") (pin "1") (pinfunction "1_1") (pintype "passive"))
      (node (ref "C27") (pin "1") (pinfunction "1_1") (pintype "passive"))
      (node (ref "C30") (pin "+") (pinfunction "+_+") (pintype "passive"))
      (node (ref "C5") (pin "+") (pinfunction "+_+") (pintype "passive"))
      (node (ref "C52") (pin "+") (pinfunction "+_+") (pintype "passive"))
      (node (ref "C53") (pin "1") (pinfunction "1_1") (pintype "passive"))
      (node (ref "F1") (pin "2") (pinfunction "2_2") (pintype "passive"))
      (node (ref "IC1") (pin "5") (pinfunction "VBUS_5") (pintype "bidirectional"))
      (node (ref "IC2") (pin "3") (pinfunction "IN_3") (pintype "input"))
      (node (ref "IC3") (pin "54") (pinfunction "VBUS_54") (pintype "bidirectional"))
      (node (ref "IC5") (pin "3") (pinfunction "IN_3") (pintype "input"))
      (node (ref "SV1") (pin "31") (pinfunction "31_31") (pintype "passive"))
      (node (ref "SV1") (pin "32") (pinfunction "32_32") (pintype "passive"))
      (node (ref "X3") (pin "1") (pinfunction "1_1") (pintype "passive"))
    )
    (net (code "100") (name "VS_AGND") (class "Default")
      (node (ref "C33") (pin "2") (pinfunction "2_2") (pintype "passive"))
      (node (ref "C34") (pin "2") (pinfunction "2_2") (pintype "passive"))
      (node (ref "C35") (pin "2") (pinfunction "2_2") (pintype "passive"))
      (node (ref "C36") (pin "1") (pinfunction "1_1") (pintype "passive"))
      (node (ref "C37") (pin "1") (pinfunction "1_1") (pintype "passive"))
      (node (ref "C39") (pin "1") (pinfunction "1_1") (pintype "passive"))
      (node (ref "C58") (pin "2") (pinfunction "2_2") (pintype "passive"))
      (node (ref "JP1") (pin "SLEEVE") (pinfunction "SLEEVE_SLEEVE") (pintype "bidirectional"))
      (node (ref "R21") (pin "2") (pinfunction "2_2") (pintype "passive"))
      (node (ref "R25") (pin "1") (pinfunction "1_1") (pintype "passive"))
      (node (ref "R33") (pin "2") (pinfunction "2_2") (pintype "passive"))
      (node (ref "R34") (pin "2") (pinfunction "2_2") (pintype "passive"))
      (node (ref "U2") (pin "37") (pinfunction "AGND_37") (pintype "power_in"))
      (node (ref "U2") (pin "40") (pinfunction "AGND1_40") (pintype "power_in"))
      (node (ref "U2") (pin "41") (pinfunction "AGND2_41") (pintype "power_in"))
      (node (ref "U2") (pin "47") (pinfunction "AGND3_47") (pintype "power_in"))
    )
    (net (code "101") (name "VS_AVDD") (class "Default")
      (node (ref "C33") (pin "1") (pinfunction "1_1") (pintype "passive"))
      (node (ref "C34") (pin "1") (pinfunction "1_1") (pintype "passive"))
      (node (ref "C35") (pin "1") (pinfunction "1_1") (pintype "passive"))
      (node (ref "C58") (pin "1") (pinfunction "1_1") (pintype "passive"))
      (node (ref "L1") (pin "1") (pinfunction "1_1") (pintype "passive"))
      (node (ref "U2") (pin "38") (pinfunction "AVDD_38") (pintype "power_in"))
      (node (ref "U2") (pin "43") (pinfunction "AVDD1_43") (pintype "power_in"))
      (node (ref "U2") (pin "45") (pinfunction "AVDD2_45") (pintype "power_in"))
    )
    (net (code "102") (name "VS_CVDD") (class "Default")
      (node (ref "C45") (pin "1") (pinfunction "1_1") (pintype "passive"))
      (node (ref "C46") (pin "1") (pinfunction "1_1") (pintype "passive"))
      (node (ref "C47") (pin "1") (pinfunction "1_1") (pintype "passive"))
      (node (ref "C48") (pin "1") (pinfunction "1_1") (pintype "passive"))
      (node (ref "C57") (pin "1") (pinfunction "1_1") (pintype "passive"))
      (node (ref "L2") (pin "1") (pinfunction "1_1") (pintype "passive"))
      (node (ref "U2") (pin "24") (pinfunction "CVDD2_24") (pintype "power_in"))
      (node (ref "U2") (pin "31") (pinfunction "CVDD3_31") (pintype "power_in"))
      (node (ref "U2") (pin "5") (pinfunction "CVDD_5") (pintype "power_in"))
      (node (ref "U2") (pin "7") (pinfunction "CVDD1_7") (pintype "power_in"))
    )
    (net (code "103") (name "VS_DREQ") (class "Default")
      (node (ref "IC3") (pin "6") (pinfunction "RC1/T2CK_6") (pintype "bidirectional"))
      (node (ref "U2") (pin "8") (pinfunction "DREQ_8") (pintype "bidirectional"))
    )
    (net (code "104") (name "VS_MISO") (class "Default")
      (node (ref "IC3") (pin "9") (pinfunction "RC4/T5CK/SDI1_9") (pintype "bidirectional"))
      (node (ref "U2") (pin "30") (pinfunction "SO_30") (pintype "bidirectional"))
    )
    (net (code "105") (name "VS_MOSI") (class "Default")
      (node (ref "IC3") (pin "72") (pinfunction "SDO1/INT0/OC1/RD0_72") (pintype "bidirectional"))
      (node (ref "U2") (pin "29") (pinfunction "SI_29") (pintype "bidirectional"))
    )
    (net (code "106") (name "VS_SCK") (class "Default")
      (node (ref "IC3") (pin "70") (pinfunction "SCKI/IC3/PMCS2/PMA15/RD10_70") (pintype "bidirectional"))
      (node (ref "U2") (pin "28") (pinfunction "SCLK_28") (pintype "bidirectional"))
    )
    (net (code "107") (name "VS_XCS") (class "Default")
      (node (ref "IC3") (pin "5") (pinfunction "RE7/PMD7_5") (pintype "bidirectional"))
      (node (ref "U2") (pin "23") (pinfunction "XCS_23") (pintype "bidirectional"))
    )
    (net (code "108") (name "VS_XDCS") (class "Default")
      (node (ref "IC3") (pin "4") (pinfunction "RE6/PMD6_4") (pintype "bidirectional"))
      (node (ref "U2") (pin "13") (pinfunction "XDCS/BSYNC_13") (pintype "bidirectional"))
    )
    (net (code "109") (name "VS_XRST") (class "Default")
      (node (ref "IC3") (pin "7") (pinfunction "RC2/T3CK/AC2TX_7") (pintype "bidirectional"))
      (node (ref "R36") (pin "1") (pinfunction "1_1") (pintype "passive"))
      (node (ref "U2") (pin "3") (pinfunction "XRESET_3") (pintype "bidirectional"))
    )
    (net (code "110") (name "_2V6") (class "Default")
      (node (ref "C51") (pin "+") (pinfunction "+_+") (pintype "passive"))
      (node (ref "C54") (pin "1") (pinfunction "1_1") (pintype "passive"))
      (node (ref "IC5") (pin "2") (pinfunction "OUT_2") (pintype "passive"))
      (node (ref "IC5") (pin "TAB") (pinfunction "OUT1_TAB") (pintype "passive"))
      (node (ref "L1") (pin "2") (pinfunction "2_2") (pintype "passive"))
      (node (ref "L2") (pin "2") (pinfunction "2_2") (pintype "passive"))
    )
    (net (code "111") (name "unconnected-(IC3-AC1RX{slash}SS3A{slash}U3BRX{slash}U3ACTS{slash}RF12-Pad40)") (class "Default")
      (node (ref "IC3") (pin "40") (pinfunction "AC1RX/SS3A/U3BRX/U3ACTS/RF12_40") (pintype "bidirectional"))
    )
    (net (code "112") (name "unconnected-(IC3-RA0{slash}TMS-Pad17)") (class "Default")
      (node (ref "IC3") (pin "17") (pinfunction "RA0/TMS_17") (pintype "bidirectional"))
    )
    (net (code "113") (name "unconnected-(IC3-RA2{slash}SCL2-Pad58)") (class "Default")
      (node (ref "IC3") (pin "58") (pinfunction "RA2/SCL2_58") (pintype "bidirectional"))
    )
    (net (code "114") (name "unconnected-(IC3-RA3{slash}SDA2-Pad59)") (class "Default")
      (node (ref "IC3") (pin "59") (pinfunction "RA3/SDA2_59") (pintype "bidirectional"))
    )
    (net (code "115") (name "unconnected-(IC3-RA4{slash}TDI-Pad60)") (class "Default")
      (node (ref "IC3") (pin "60") (pinfunction "RA4/TDI_60") (pintype "bidirectional"))
    )
    (net (code "116") (name "unconnected-(IC3-RA5{slash}TDO-Pad61)") (class "Default")
      (node (ref "IC3") (pin "61") (pinfunction "RA5/TDO_61") (pintype "bidirectional"))
    )
    (net (code "117") (name "unconnected-(IC3-RA9{slash}VR-{slash}PMA7{slash}CVREF-{slash}AERXD2-Pad28)") (class "Default")
      (node (ref "IC3") (pin "28") (pinfunction "RA9/VR-/PMA7/CVREF-/AERXD2_28") (pintype "bidirectional"))
    )
    (net (code "118") (name "unconnected-(IC3-RA10{slash}VR+{slash}CVREF+{slash}AERXD3{slash}PMA6-Pad29)") (class "Default")
      (node (ref "IC3") (pin "29") (pinfunction "RA10/VR+/CVREF+/AERXD3/PMA6_29") (pintype "bidirectional"))
    )
    (net (code "119") (name "unconnected-(IC3-RB2{slash}AN2{slash}CN4{slash}C2IN--Pad23)") (class "Default")
      (node (ref "IC3") (pin "23") (pinfunction "RB2/AN2/CN4/C2IN-_23") (pintype "bidirectional"))
    )
    (net (code "120") (name "unconnected-(IC3-RB3{slash}AN3{slash}CN5{slash}C2IN+-Pad22)") (class "Default")
      (node (ref "IC3") (pin "22") (pinfunction "RB3/AN3/CN5/C2IN+_22") (pintype "bidirectional"))
    )
    (net (code "121") (name "unconnected-(IC3-RB4{slash}AN4{slash}CN6{slash}C1IN--Pad21)") (class "Default")
      (node (ref "IC3") (pin "21") (pinfunction "RB4/AN4/CN6/C1IN-_21") (pintype "bidirectional"))
    )
    (net (code "122") (name "unconnected-(IC3-RB5{slash}AN5{slash}CN7{slash}C1IN+{slash}VBUSON-Pad20)") (class "Default")
      (node (ref "IC3") (pin "20") (pinfunction "RB5/AN5/CN7/C1IN+/VBUSON_20") (pintype "bidirectional"))
    )
    (net (code "123") (name "unconnected-(IC3-RB6{slash}AN6{slash}PGC2{slash}OCFA-Pad26)") (class "Default")
      (node (ref "IC3") (pin "26") (pinfunction "RB6/AN6/PGC2/OCFA_26") (pintype "bidirectional"))
    )
    (net (code "124") (name "unconnected-(IC3-RB7{slash}AN7{slash}PGD2-Pad27)") (class "Default")
      (node (ref "IC3") (pin "27") (pinfunction "RB7/AN7/PGD2_27") (pintype "bidirectional"))
    )
    (net (code "125") (name "unconnected-(IC3-RB8{slash}AN8{slash}C1OUT-Pad32)") (class "Default")
      (node (ref "IC3") (pin "32") (pinfunction "RB8/AN8/C1OUT_32") (pintype "bidirectional"))
    )
    (net (code "126") (name "unconnected-(IC3-RB9{slash}AN9{slash}C2OUT-Pad33)") (class "Default")
      (node (ref "IC3") (pin "33") (pinfunction "RB9/AN9/C2OUT_33") (pintype "bidirectional"))
    )
    (net (code "127") (name "unconnected-(IC3-RB14{slash}AN14{slash}PMA1{slash}ERXD2{slash}AETXD3{slash}-Pad43)") (class "Default")
      (node (ref "IC3") (pin "43") (pinfunction "RB14/AN14/PMA1/ERXD2/AETXD3/_43") (pintype "bidirectional"))
    )
    (net (code "128") (name "unconnected-(IC3-RE8{slash}INT1{slash}AERXD0-Pad18)") (class "Default")
      (node (ref "IC3") (pin "18") (pinfunction "RE8/INT1/AERXD0_18") (pintype "bidirectional"))
    )
    (net (code "129") (name "unconnected-(IC3-RE9{slash}INT2{slash}AERXD1-Pad19)") (class "Default")
      (node (ref "IC3") (pin "19") (pinfunction "RE9/INT2/AERXD1_19") (pintype "bidirectional"))
    )
    (net (code "130") (name "unconnected-(IC4-CLK2MAC-Pad25)") (class "Default")
      (node (ref "IC4") (pin "25") (pinfunction "CLK2MAC_25") (pintype "bidirectional"))
    )
    (net (code "131") (name "unconnected-(IC4-COL-Pad42)") (class "Default")
      (node (ref "IC4") (pin "42") (pinfunction "COL_42") (pintype "bidirectional"))
    )
    (net (code "132") (name "unconnected-(IC4-LED_SPD-Pad27)") (class "Default")
      (node (ref "IC4") (pin "27") (pinfunction "LED_SPD_27") (pintype "bidirectional"))
    )
    (net (code "133") (name "unconnected-(IC4-RXD_2-Pad45)") (class "Default")
      (node (ref "IC4") (pin "45") (pinfunction "RXD_2_45") (pintype "bidirectional"))
    )
    (net (code "134") (name "unconnected-(IC4-RXD_3-Pad46)") (class "Default")
      (node (ref "IC4") (pin "46") (pinfunction "RXD_3_46") (pintype "bidirectional"))
    )
    (net (code "135") (name "unconnected-(IC4-RX_CLK-Pad38)") (class "Default")
      (node (ref "IC4") (pin "38") (pinfunction "RX_CLK_38") (pintype "bidirectional"))
    )
    (net (code "136") (name "unconnected-(IC4-TCK-Pad8)") (class "Default")
      (node (ref "IC4") (pin "8") (pinfunction "TCK_8") (pintype "input"))
    )
    (net (code "137") (name "unconnected-(IC4-TDI-Pad12)") (class "Default")
      (node (ref "IC4") (pin "12") (pinfunction "TDI_12") (pintype "input"))
    )
    (net (code "138") (name "unconnected-(IC4-TDO-Pad9)") (class "Default")
      (node (ref "IC4") (pin "9") (pinfunction "TDO_9") (pintype "output"))
    )
    (net (code "139") (name "unconnected-(IC4-TMS-Pad10)") (class "Default")
      (node (ref "IC4") (pin "10") (pinfunction "TMS_10") (pintype "input"))
    )
    (net (code "140") (name "unconnected-(IC4-TRST_N-Pad11)") (class "Default")
      (node (ref "IC4") (pin "11") (pinfunction "TRST_N_11") (pintype "input"))
    )
    (net (code "141") (name "unconnected-(IC4-TXD_2-Pad5)") (class "Default")
      (node (ref "IC4") (pin "5") (pinfunction "TXD_2_5") (pintype "bidirectional"))
    )
    (net (code "142") (name "unconnected-(IC4-TX_CLK-Pad1)") (class "Default")
      (node (ref "IC4") (pin "1") (pinfunction "TX_CLK_1") (pintype "bidirectional"))
    )
    (net (code "143") (name "unconnected-(IC4-X2-Pad33)") (class "Default")
      (node (ref "IC4") (pin "33") (pinfunction "X2_33") (pintype "output"))
    )
    (net (code "144") (name "unconnected-(JP2-Pad2)") (class "Default")
      (node (ref "JP2") (pin "2") (pinfunction "2_2") (pintype "passive"))
    )
    (net (code "145") (name "unconnected-(JP2-Pad6)") (class "Default")
      (node (ref "JP2") (pin "6") (pinfunction "6_6") (pintype "passive"))
    )
    (net (code "146") (name "unconnected-(JP5-D+-PadD+1)") (class "Default")
      (node (ref "JP5") (pin "D+1") (pinfunction "D+_D+1") (pintype "bidirectional"))
    )
    (net (code "147") (name "unconnected-(JP5-D--PadD-1)") (class "Default")
      (node (ref "JP5") (pin "D-1") (pinfunction "D-_D-1") (pintype "bidirectional"))
    )
    (net (code "148") (name "unconnected-(JP5-ID-PadID1)") (class "Default")
      (node (ref "JP5") (pin "ID1") (pinfunction "ID_ID1") (pintype "bidirectional"))
    )
    (net (code "149") (name "unconnected-(RJ1-PadNC)") (class "Default")
      (node (ref "RJ1") (pin "NC") (pinfunction "NC_NC") (pintype "bidirectional"))
    )
    (net (code "150") (name "unconnected-(SV1-Pad8)") (class "Default")
      (node (ref "SV1") (pin "8") (pinfunction "8_8") (pintype "passive"))
    )
    (net (code "151") (name "unconnected-(U$1-TRI-Pad1)") (class "Default")
      (node (ref "U$1") (pin "1") (pinfunction "TRI_1") (pintype "input"))
    )
    (net (code "152") (name "unconnected-(U$7-TRI-Pad1)") (class "Default")
      (node (ref "U$7") (pin "1") (pinfunction "TRI_1") (pintype "input"))
    )
    (net (code "153") (name "unconnected-(U1-NC-Pad1)") (class "Default")
      (node (ref "U1") (pin "1") (pinfunction "NC_1") (pintype "bidirectional"))
    )
    (net (code "154") (name "unconnected-(U1-RSV-Pad8)") (class "Default")
      (node (ref "U1") (pin "8") (pinfunction "RSV_8") (pintype "bidirectional"))
    )
    (net (code "155") (name "unconnected-(U2A-LINEIN-Pad48)") (class "Default")
      (node (ref "U2") (pin "48") (pinfunction "LINEIN_48") (pintype "bidirectional"))
    )
    (net (code "156") (name "unconnected-(U2A-MICN-Pad2)") (class "Default")
      (node (ref "U2") (pin "2") (pinfunction "MICN_2") (pintype "bidirectional"))
    )
    (net (code "157") (name "unconnected-(U2A-MICP-Pad1)") (class "Default")
      (node (ref "U2") (pin "1") (pinfunction "MICP_1") (pintype "bidirectional"))
    )
    (net (code "158") (name "unconnected-(U2A-TX-Pad27)") (class "Default")
      (node (ref "U2") (pin "27") (pinfunction "TX_27") (pintype "bidirectional"))
    )
    (net (code "159") (name "unconnected-(U2A-VCO-Pad15)") (class "Default")
      (node (ref "U2") (pin "15") (pinfunction "VCO_15") (pintype "bidirectional"))
    )
  )
)
